# headstage.net
KiCad netlist of a schematic drawn in EAGLE
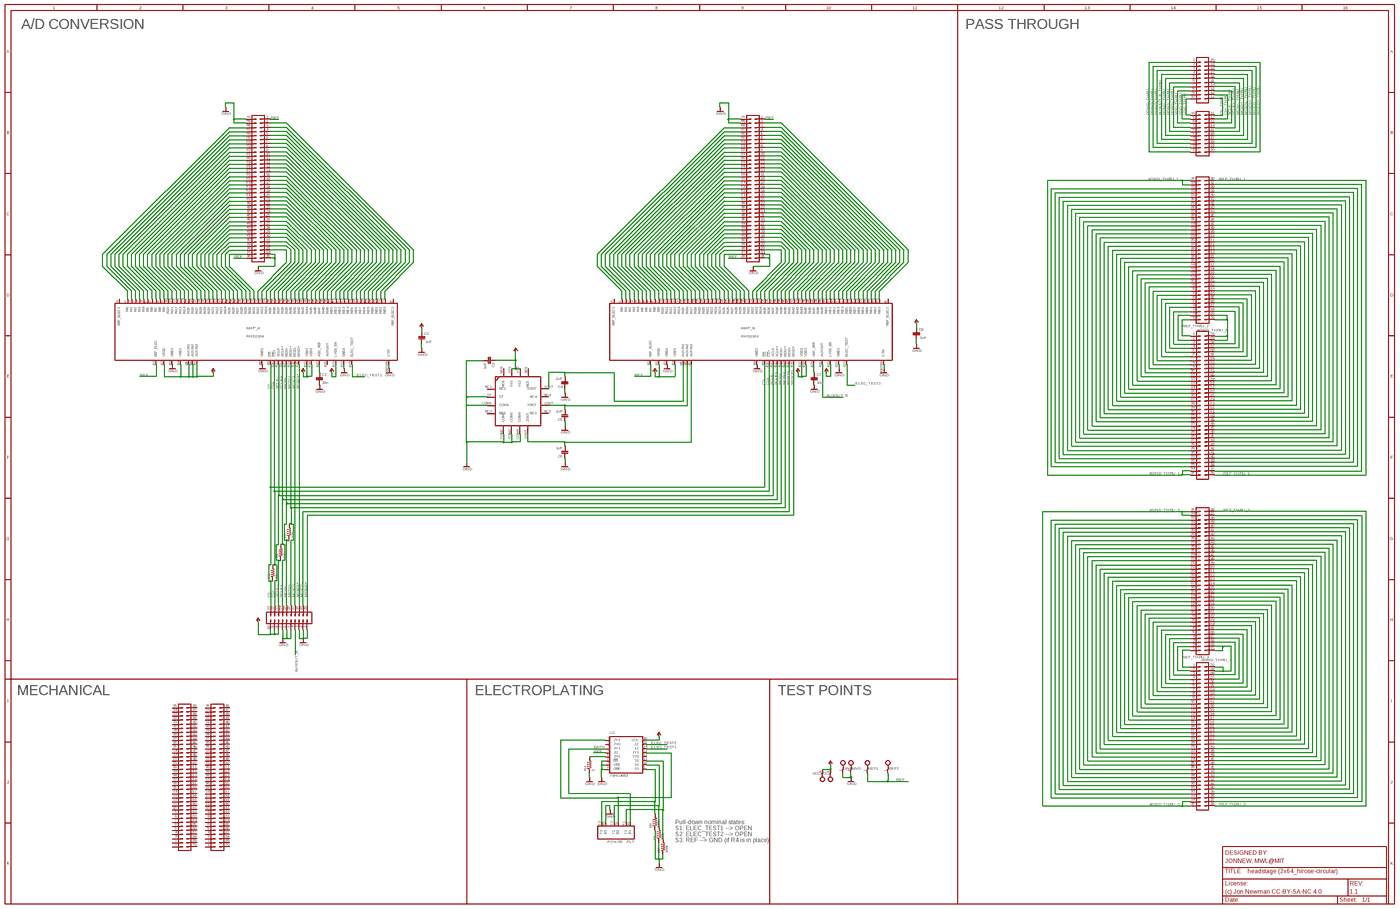
[diagram p0: schematic, sheet 1, overview]
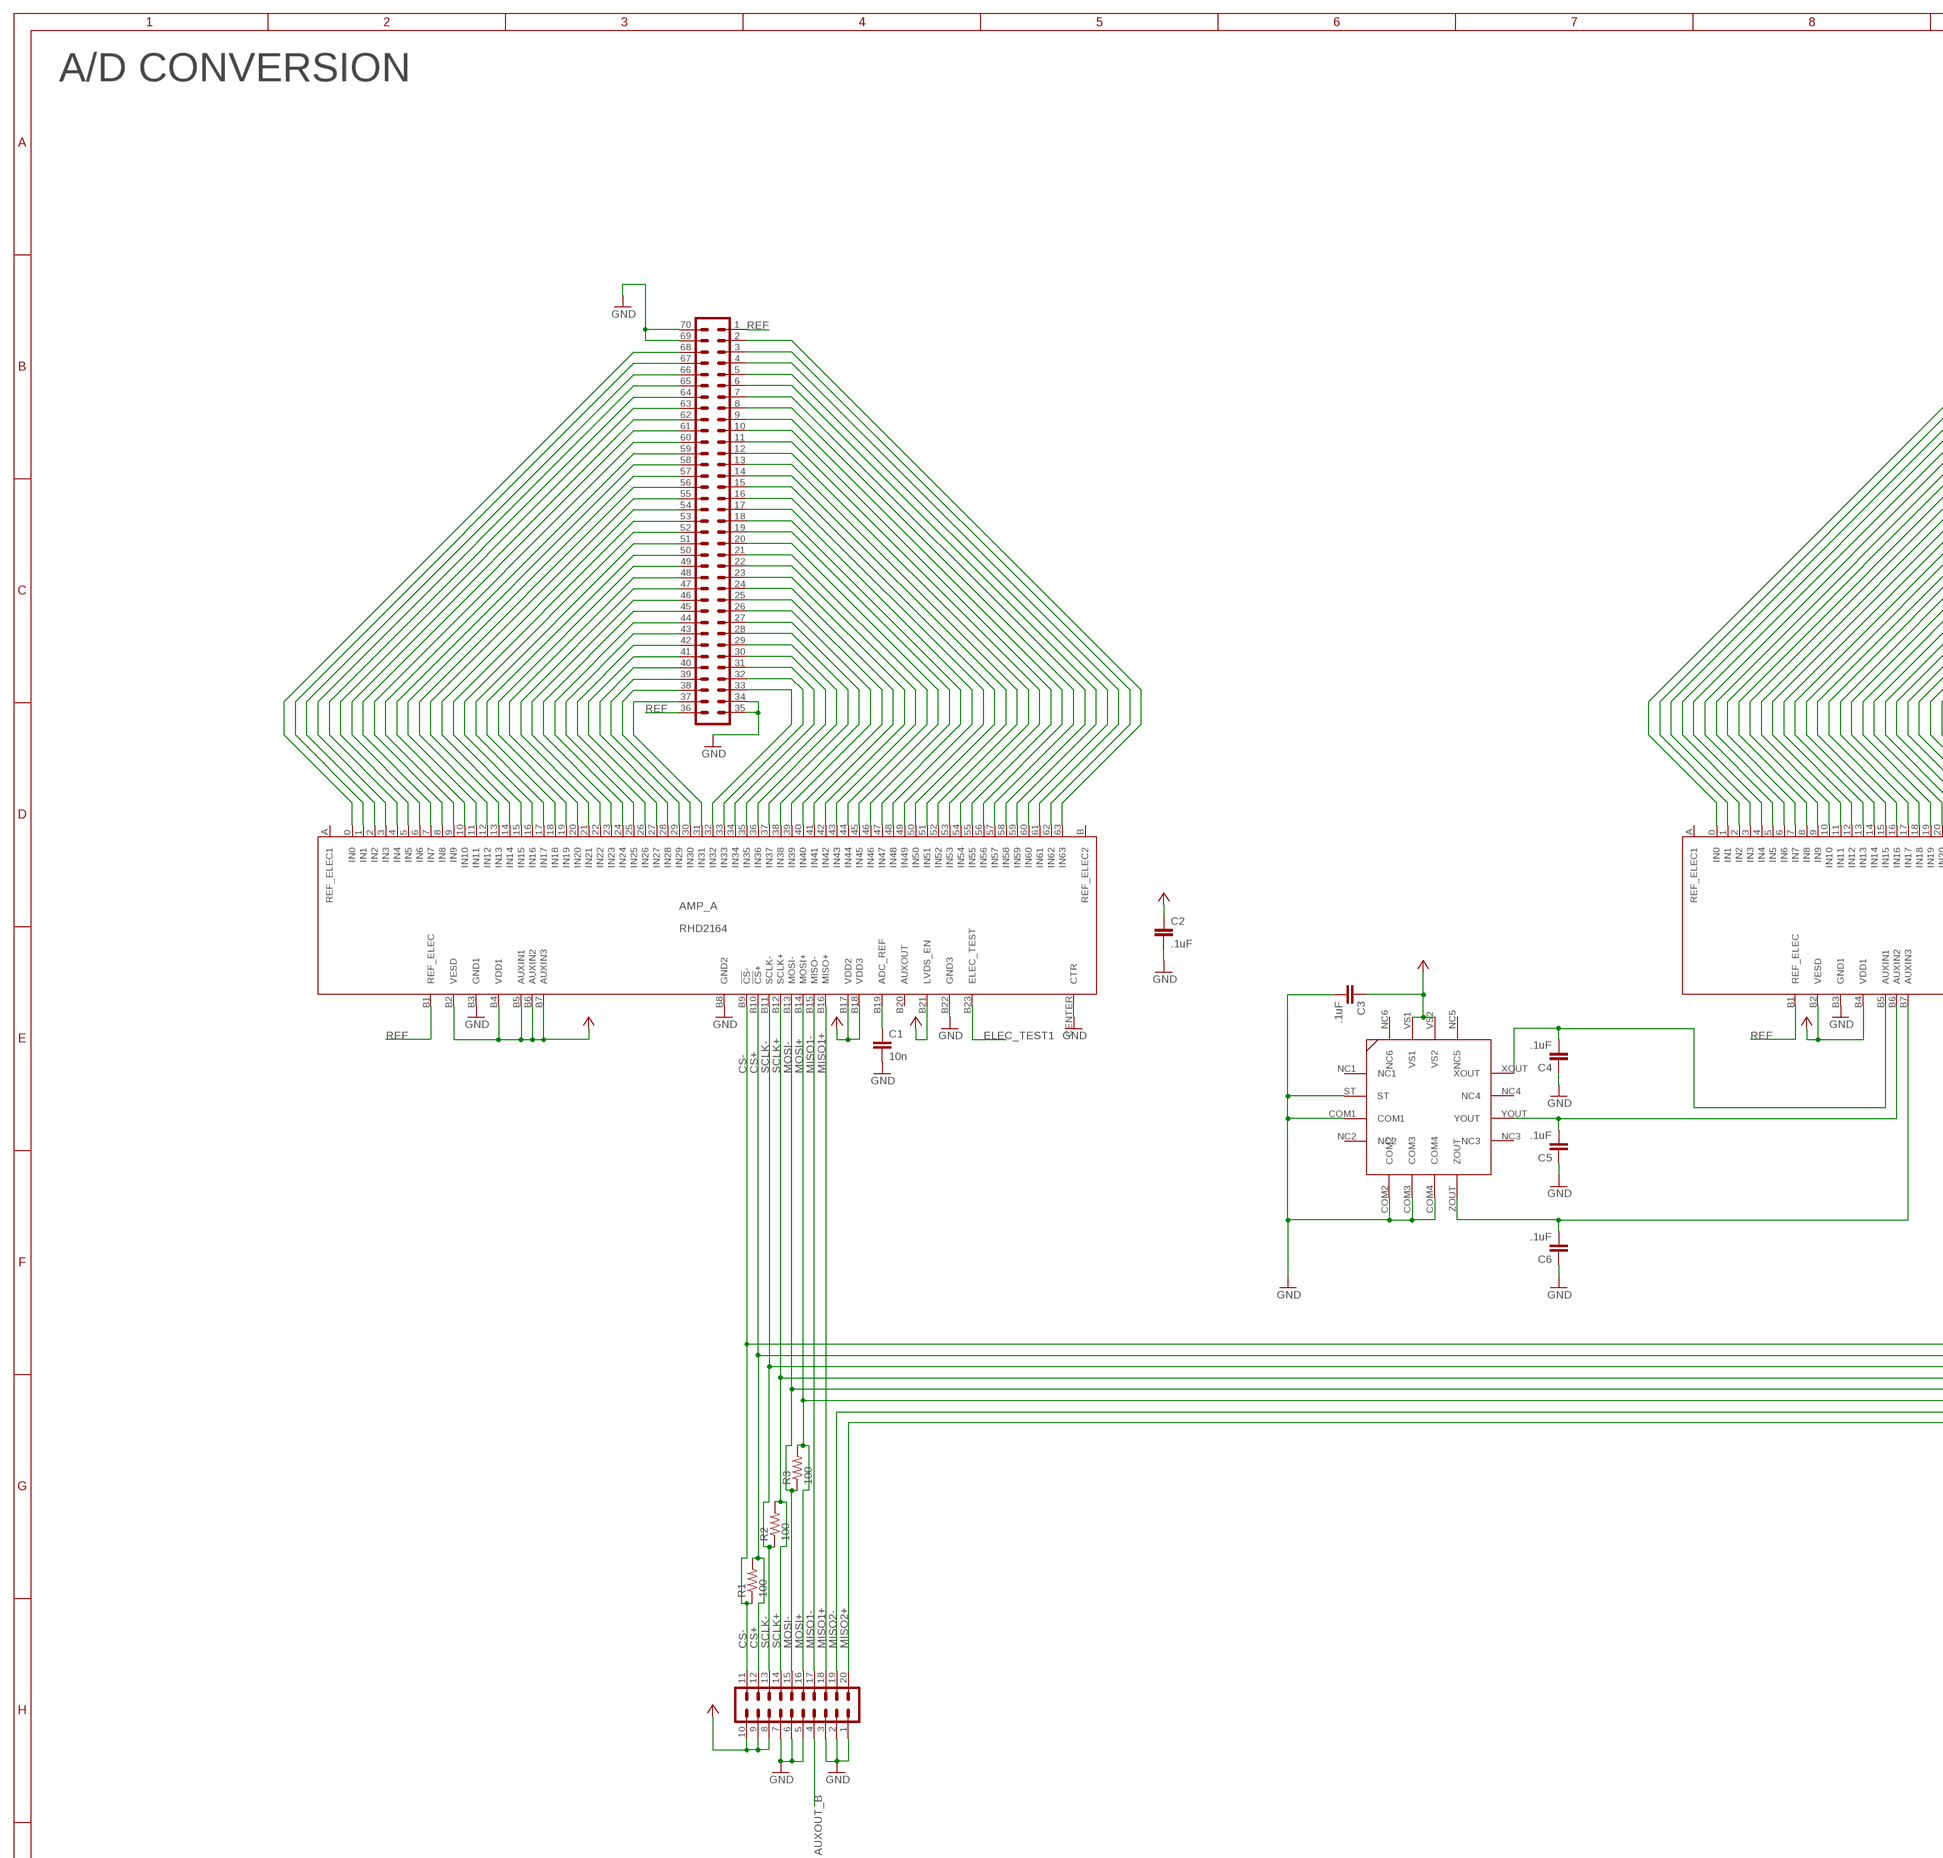
[diagram p1: schematic, sheet 1, part 1 of 4]
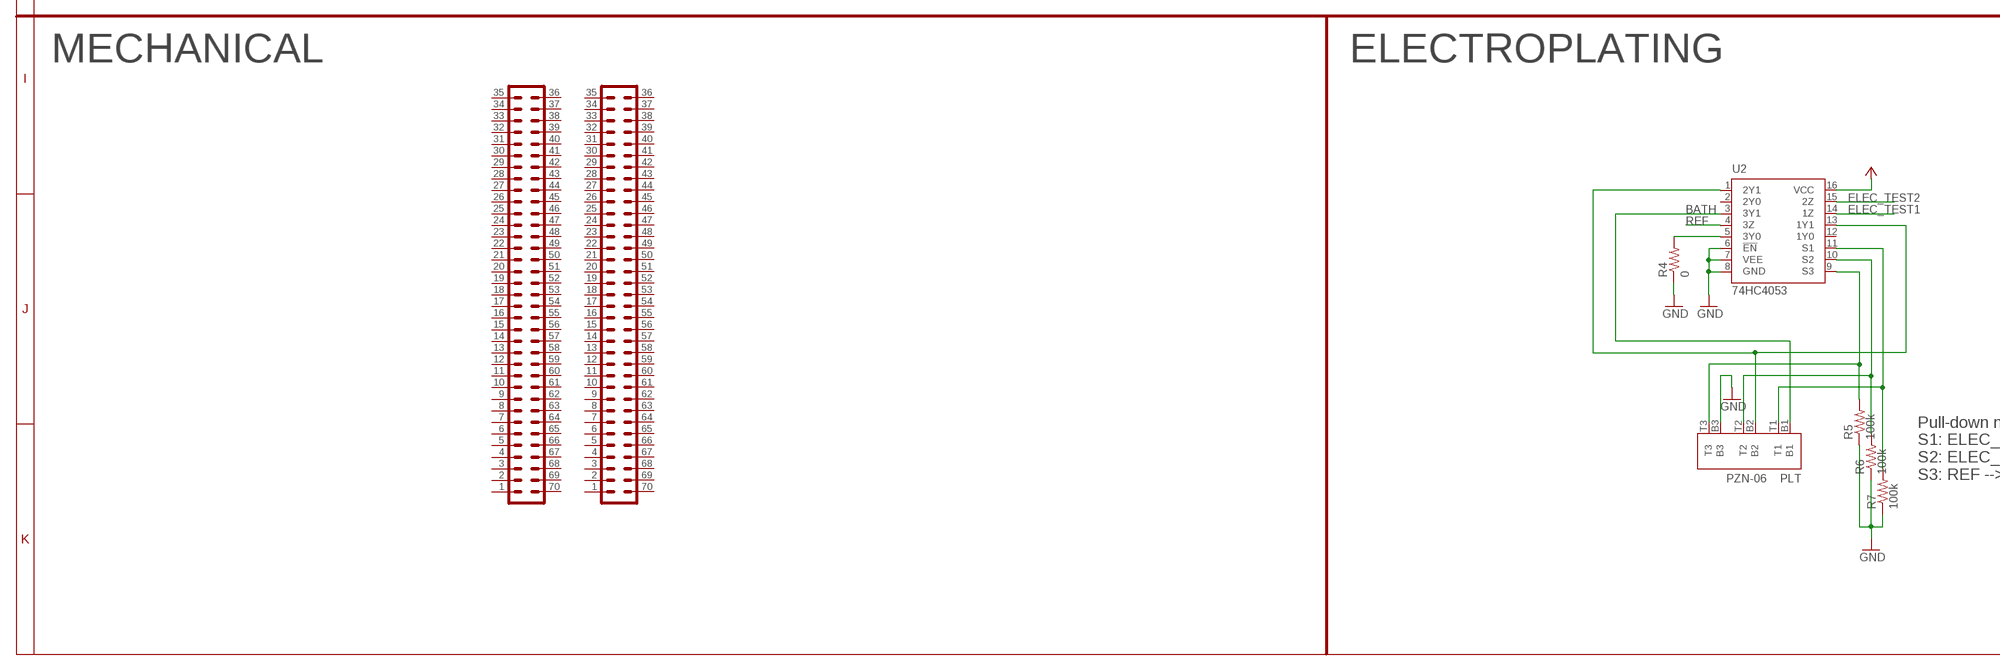
[diagram p2: schematic, sheet 1, part 2 of 4]
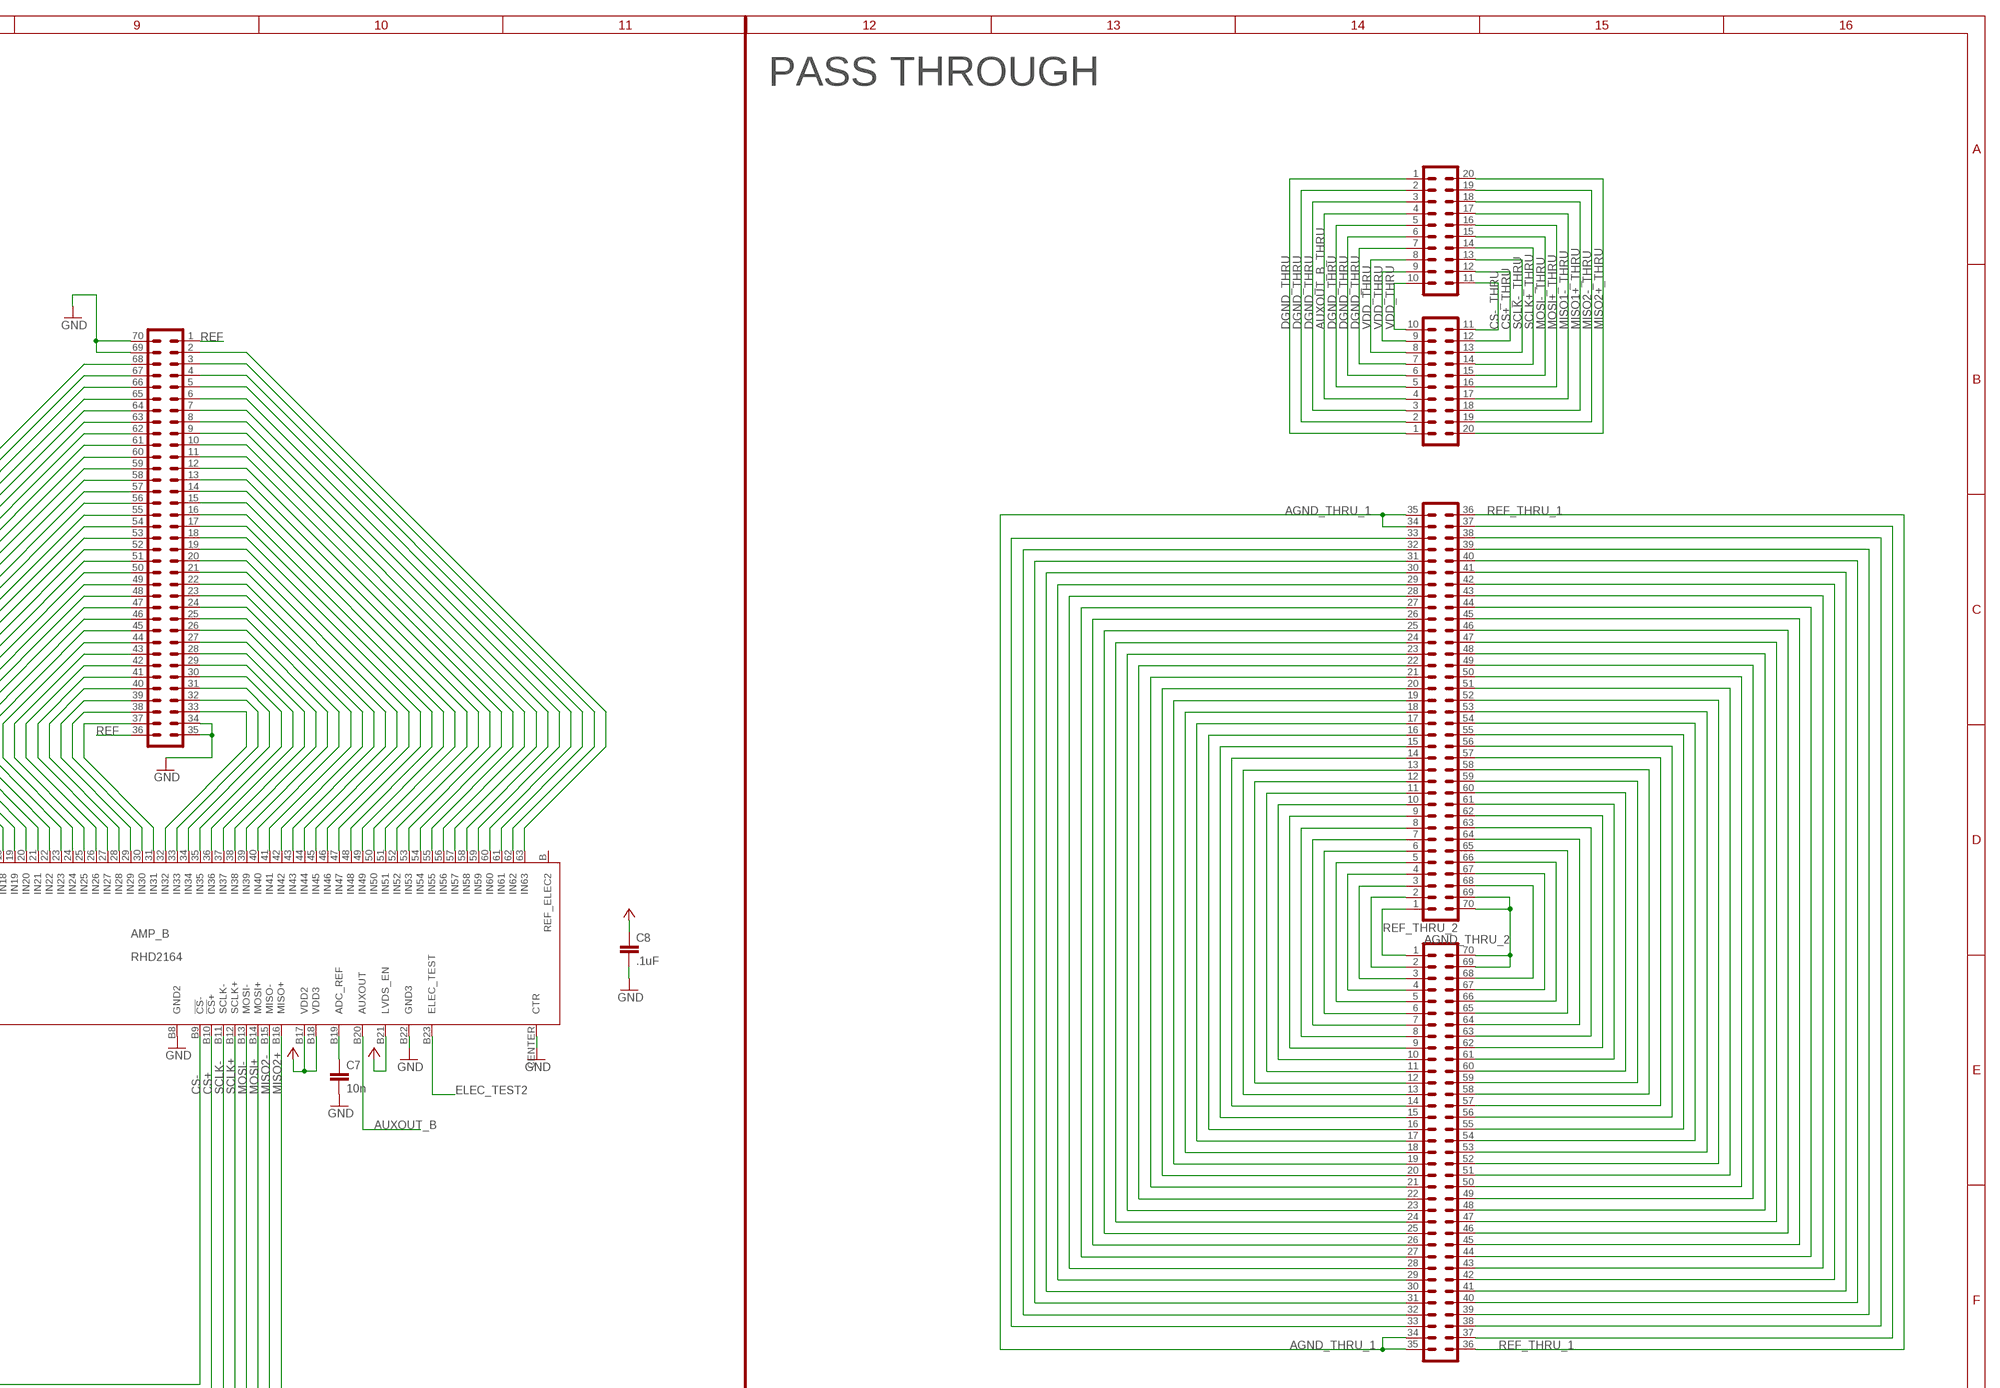
[diagram p3: schematic, sheet 1, part 3 of 4]
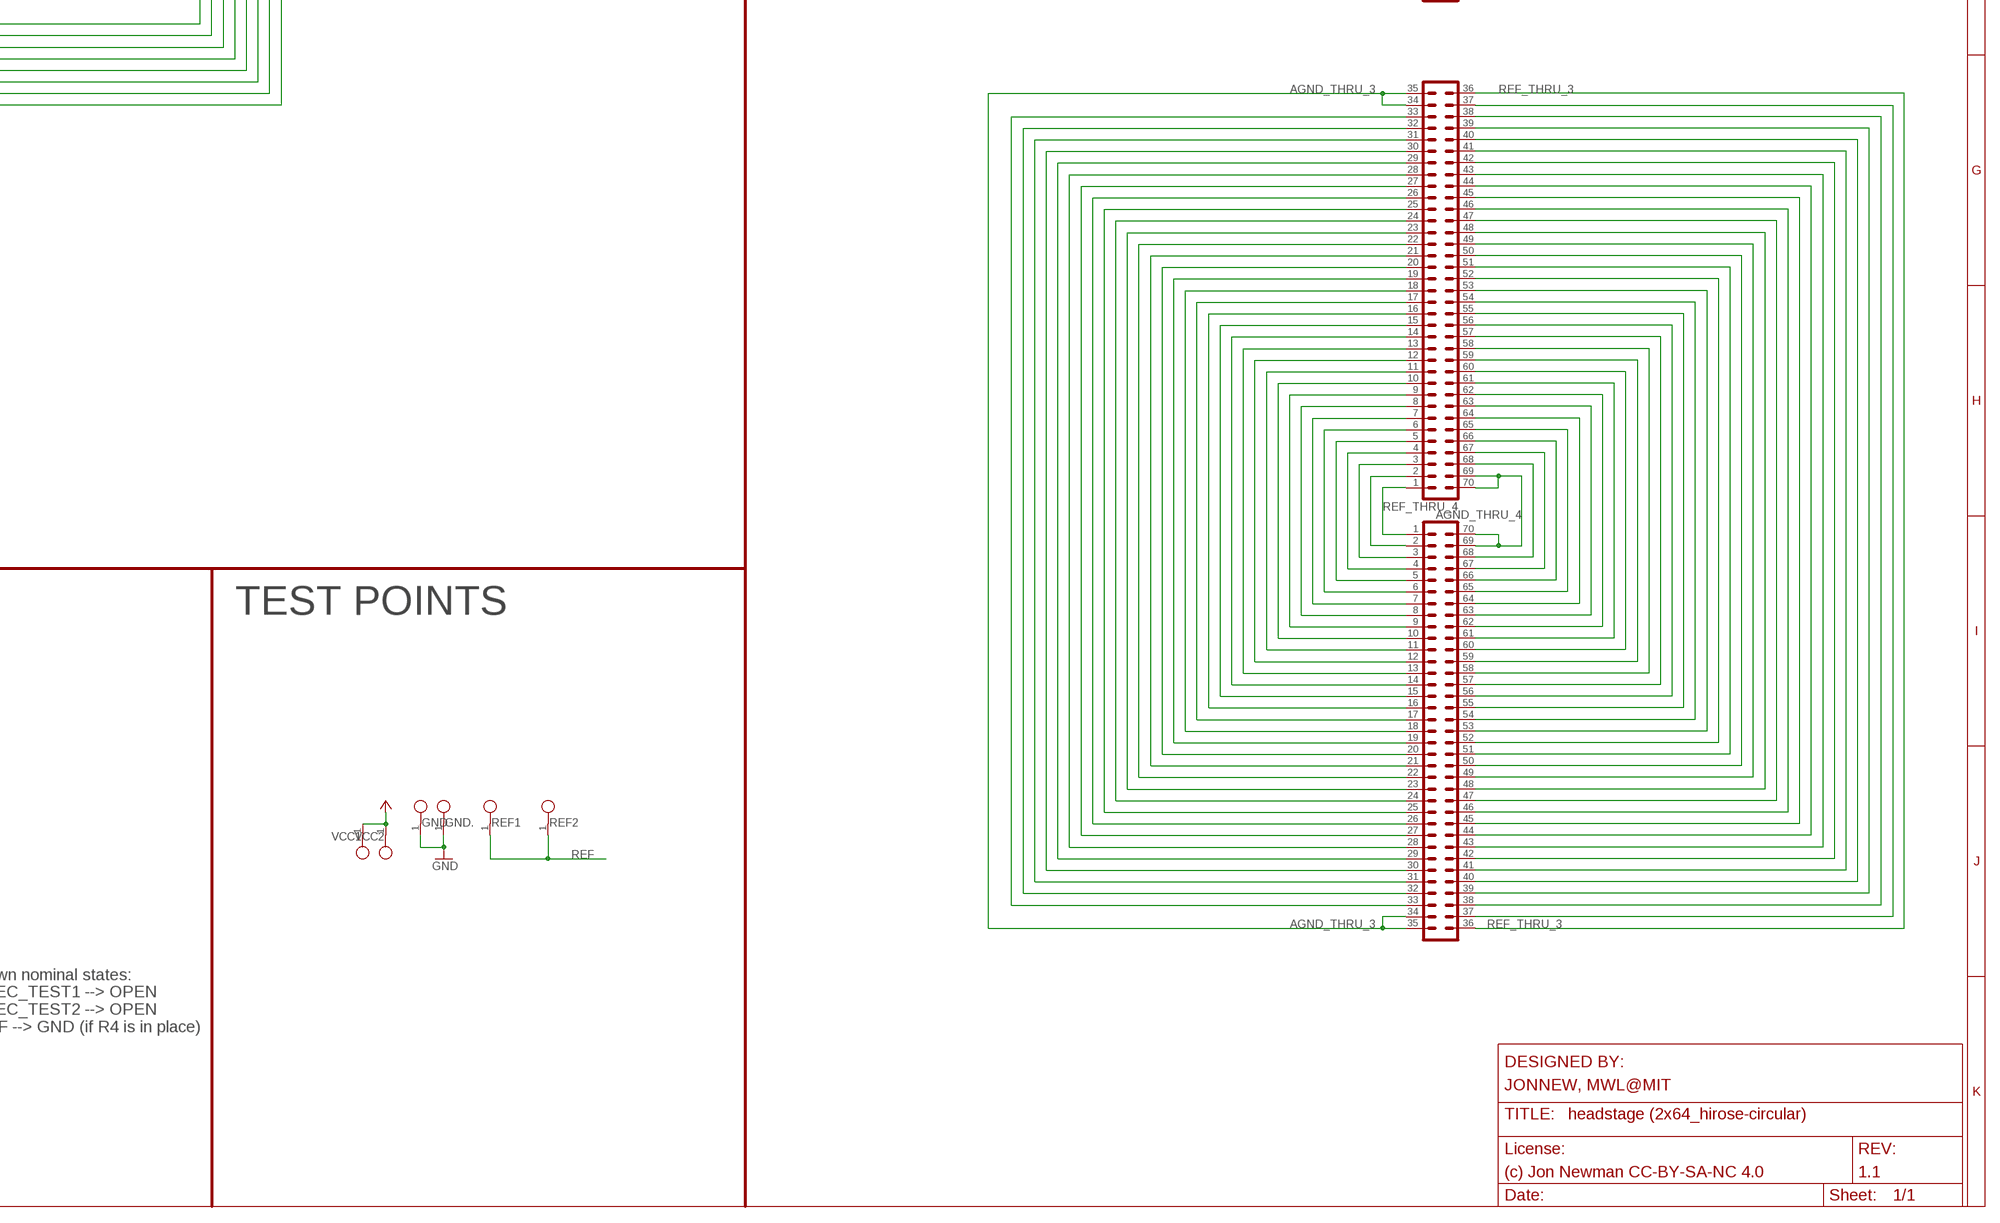
[diagram p4: schematic, sheet 1, part 4 of 4]

(export (version "E")
  (design (tool "Eeschema 10.0.6"))
  (components
    (comp (ref "AIN_BNB")
      (value "DF40REC")
      (footprint "eagle-import:DF40-70REC")
      (libsource (lib "eagle-import") (part "PINHD-2X35_DF40REC"))
    )
    (comp (ref "AIN_BSB")
      (value "DF40REC")
      (footprint "eagle-import:DF40-70REC")
      (libsource (lib "eagle-import") (part "PINHD-2X35_DF40REC"))
    )
    (comp (ref "AMP_A")
      (value "RHD2164")
      (footprint "eagle-import:RHD2164_COB")
      (libsource (lib "eagle-import") (part "RHD2164_COB"))
    )
    (comp (ref "AMP_B")
      (value "RHD2164")
      (footprint "eagle-import:RHD2164_COB")
      (libsource (lib "eagle-import") (part "RHD2164_COB"))
    )
    (comp (ref "ATHRU_BEB")
      (value "DF40REC")
      (footprint "eagle-import:DF40-70REC")
      (libsource (lib "eagle-import") (part "PINHD-2X35_DF40REC"))
    )
    (comp (ref "ATHRU_BWB")
      (value "DF40REC")
      (footprint "eagle-import:DF40-70REC")
      (libsource (lib "eagle-import") (part "PINHD-2X35_DF40REC"))
    )
    (comp (ref "ATHRU_TEB")
      (value "DF40HEAD")
      (footprint "eagle-import:DF40-70HEAD")
      (libsource (lib "eagle-import") (part "PINHD-2X35_DF40HEAD"))
    )
    (comp (ref "ATHRU_TWB")
      (value "DF40HEAD")
      (footprint "eagle-import:DF40-70HEAD")
      (libsource (lib "eagle-import") (part "PINHD-2X35_DF40HEAD"))
    )
    (comp (ref "C1")
      (value "10n")
      (footprint "eagle-import:0201")
      (libsource (lib "eagle-import") (part "C_0201"))
    )
    (comp (ref "C2")
      (value ".1uF")
      (footprint "eagle-import:0402")
      (libsource (lib "eagle-import") (part "C_0402"))
    )
    (comp (ref "C3")
      (value ".1uF")
      (footprint "eagle-import:0402")
      (libsource (lib "eagle-import") (part "headstage_C_0402"))
    )
    (comp (ref "C4")
      (value ".1uF")
      (footprint "eagle-import:0402")
      (libsource (lib "eagle-import") (part "jonnew_C_0402"))
    )
    (comp (ref "C5")
      (value ".1uF")
      (footprint "eagle-import:0402")
      (libsource (lib "eagle-import") (part "jonnew_C_0402"))
    )
    (comp (ref "C6")
      (value ".1uF")
      (footprint "eagle-import:0402")
      (libsource (lib "eagle-import") (part "jonnew_C_0402"))
    )
    (comp (ref "C7")
      (value "10n")
      (footprint "eagle-import:0201")
      (libsource (lib "eagle-import") (part "C_0201"))
    )
    (comp (ref "C8")
      (value ".1uF")
      (footprint "eagle-import:0402")
      (libsource (lib "eagle-import") (part "C_0402"))
    )
    (comp (ref "DIO_TEA")
      (value "DF40HEAD")
      (footprint "eagle-import:DF40-20HEAD")
      (libsource (lib "eagle-import") (part "PINHD-2X10_DF40-20HEAD"))
    )
    (comp (ref "DTHRU_BNA")
      (value "DF40REC")
      (footprint "eagle-import:DF40-20REC")
      (libsource (lib "eagle-import") (part "PINHD-2X10_DF40-20REC"))
    )
    (comp (ref "DTHRU_TNA")
      (value "DF40HEAD")
      (footprint "eagle-import:DF40-20HEAD")
      (libsource (lib "eagle-import") (part "PINHD-2X10_DF40-20HEAD"))
    )
    (comp (ref "GND")
      (value "GND")
      (footprint "eagle-import:TESTPOINT_SMALL")
      (libsource (lib "eagle-import") (part "TESTPOINT_SMALL"))
    )
    (comp (ref "GND.")
      (value "GND")
      (footprint "eagle-import:TESTPOINT_SMALL")
      (libsource (lib "eagle-import") (part "TESTPOINT_SMALL"))
    )
    (comp (ref "MECH_TNB")
      (value "DF40HEAD")
      (footprint "eagle-import:DF40-70HEAD")
      (libsource (lib "eagle-import") (part "PINHD-2X35_DF40HEAD"))
    )
    (comp (ref "MECH_TSB")
      (value "DF40HEAD")
      (footprint "eagle-import:DF40-70HEAD")
      (libsource (lib "eagle-import") (part "PINHD-2X35_DF40HEAD"))
    )
    (comp (ref "PLT")
      (value "PZN-06")
      (footprint "eagle-import:OMNETICS_PZN-06-AA")
      (libsource (lib "eagle-import") (part "OMNETICS_PZN-06_SMD"))
    )
    (comp (ref "R1")
      (value "100")
      (footprint "eagle-import:0201")
      (libsource (lib "eagle-import") (part "jonnew_R_0201"))
    )
    (comp (ref "R2")
      (value "100")
      (footprint "eagle-import:0201")
      (libsource (lib "eagle-import") (part "jonnew_R_0201"))
    )
    (comp (ref "R3")
      (value "100")
      (footprint "eagle-import:0201")
      (libsource (lib "eagle-import") (part "jonnew_R_0201"))
    )
    (comp (ref "R4")
      (value "0")
      (footprint "eagle-import:0402")
      (libsource (lib "eagle-import") (part "R_0402"))
    )
    (comp (ref "R5")
      (value "100k")
      (footprint "eagle-import:0201")
      (libsource (lib "eagle-import") (part "R_0201"))
    )
    (comp (ref "R6")
      (value "100k")
      (footprint "eagle-import:0201")
      (libsource (lib "eagle-import") (part "R_0201"))
    )
    (comp (ref "R7")
      (value "100k")
      (footprint "eagle-import:0201")
      (libsource (lib "eagle-import") (part "R_0201"))
    )
    (comp (ref "REF1")
      (value "REF")
      (footprint "eagle-import:TESTPOINT_SMALL")
      (libsource (lib "eagle-import") (part "TESTPOINT_SMALL"))
    )
    (comp (ref "REF2")
      (value "REF")
      (footprint "eagle-import:TESTPOINT_SMALL")
      (libsource (lib "eagle-import") (part "TESTPOINT_SMALL"))
    )
    (comp (ref "U1")
      (value "ADXL335")
      (footprint "eagle-import:ADXL335")
      (libsource (lib "eagle-import") (part "ADXL335"))
    )
    (comp (ref "U2")
      (value "74HC4053")
      (footprint "eagle-import:TSSOP-16")
      (libsource (lib "eagle-import") (part "74HC4053_TSSOP-16"))
    )
    (comp (ref "VCC1")
      (value "VCC")
      (footprint "eagle-import:TESTPOINT_SMALL")
      (libsource (lib "eagle-import") (part "TESTPOINT_SMALL"))
    )
    (comp (ref "VCC2")
      (value "VCC")
      (footprint "eagle-import:TESTPOINT_SMALL")
      (libsource (lib "eagle-import") (part "TESTPOINT_SMALL"))
    )
  )
  (nets
    (net (code "1") (name "/AGND_THRU_1") (class "Default")
      (node (ref "ATHRU_BWB") (pin "34") (pinfunction "34_34") (pintype "bidirectional"))
      (node (ref "ATHRU_BWB") (pin "35") (pinfunction "35_35") (pintype "bidirectional"))
      (node (ref "ATHRU_TWB") (pin "34") (pinfunction "34_34") (pintype "bidirectional"))
      (node (ref "ATHRU_TWB") (pin "35") (pinfunction "35_35") (pintype "bidirectional"))
    )
    (net (code "2") (name "/AGND_THRU_2") (class "Default")
      (node (ref "ATHRU_BWB") (pin "69") (pinfunction "69_69") (pintype "bidirectional"))
      (node (ref "ATHRU_BWB") (pin "70") (pinfunction "70_70") (pintype "bidirectional"))
      (node (ref "ATHRU_TWB") (pin "69") (pinfunction "69_69") (pintype "bidirectional"))
      (node (ref "ATHRU_TWB") (pin "70") (pinfunction "70_70") (pintype "bidirectional"))
    )
    (net (code "3") (name "/AGND_THRU_3") (class "Default")
      (node (ref "ATHRU_BEB") (pin "34") (pinfunction "34_34") (pintype "bidirectional"))
      (node (ref "ATHRU_BEB") (pin "35") (pinfunction "35_35") (pintype "bidirectional"))
      (node (ref "ATHRU_TEB") (pin "34") (pinfunction "34_34") (pintype "bidirectional"))
      (node (ref "ATHRU_TEB") (pin "35") (pinfunction "35_35") (pintype "bidirectional"))
    )
    (net (code "4") (name "/AGND_THRU_4") (class "Default")
      (node (ref "ATHRU_BEB") (pin "69") (pinfunction "69_69") (pintype "bidirectional"))
      (node (ref "ATHRU_BEB") (pin "70") (pinfunction "70_70") (pintype "bidirectional"))
      (node (ref "ATHRU_TEB") (pin "69") (pinfunction "69_69") (pintype "bidirectional"))
      (node (ref "ATHRU_TEB") (pin "70") (pinfunction "70_70") (pintype "bidirectional"))
    )
    (net (code "5") (name "/AUXOUT_B") (class "Default")
      (node (ref "AMP_B") (pin "B20") (pinfunction "AUXOUT_B20") (pintype "tri_state"))
      (node (ref "DIO_TEA") (pin "4") (pinfunction "4_4") (pintype "bidirectional"))
    )
    (net (code "6") (name "/AUXOUT_B_THRU") (class "Default")
      (node (ref "DTHRU_BNA") (pin "4") (pinfunction "4_4") (pintype "bidirectional"))
      (node (ref "DTHRU_TNA") (pin "4") (pinfunction "4_4") (pintype "bidirectional"))
    )
    (net (code "7") (name "/BATH") (class "Default")
      (node (ref "PLT") (pin "B1") (pinfunction "B1_B1") (pintype "bidirectional"))
      (node (ref "U2") (pin "3") (pinfunction "3Y1_3") (pintype "bidirectional"))
    )
    (net (code "8") (name "/CS+") (class "Default")
      (node (ref "AMP_A") (pin "B10") (pinfunction "~{CS}+_B10") (pintype "input"))
      (node (ref "AMP_B") (pin "B10") (pinfunction "~{CS}+_B10") (pintype "input"))
      (node (ref "DIO_TEA") (pin "12") (pinfunction "12_12") (pintype "bidirectional"))
      (node (ref "R1") (pin "2") (pinfunction "2_2") (pintype "passive"))
    )
    (net (code "9") (name "/CS+_THRU") (class "Default")
      (node (ref "DTHRU_BNA") (pin "12") (pinfunction "12_12") (pintype "bidirectional"))
      (node (ref "DTHRU_TNA") (pin "12") (pinfunction "12_12") (pintype "bidirectional"))
    )
    (net (code "10") (name "/CS-") (class "Default")
      (node (ref "AMP_A") (pin "B9") (pinfunction "~{CS}-_B9") (pintype "input"))
      (node (ref "AMP_B") (pin "B9") (pinfunction "~{CS}-_B9") (pintype "input"))
      (node (ref "DIO_TEA") (pin "11") (pinfunction "11_11") (pintype "bidirectional"))
      (node (ref "R1") (pin "1") (pinfunction "1_1") (pintype "passive"))
    )
    (net (code "11") (name "/CS-_THRU") (class "Default")
      (node (ref "DTHRU_BNA") (pin "11") (pinfunction "11_11") (pintype "bidirectional"))
      (node (ref "DTHRU_TNA") (pin "11") (pinfunction "11_11") (pintype "bidirectional"))
    )
    (net (code "12") (name "/DGND_THRU") (class "Default")
      (node (ref "DTHRU_BNA") (pin "1") (pinfunction "1_1") (pintype "bidirectional"))
      (node (ref "DTHRU_BNA") (pin "2") (pinfunction "2_2") (pintype "bidirectional"))
      (node (ref "DTHRU_BNA") (pin "3") (pinfunction "3_3") (pintype "bidirectional"))
      (node (ref "DTHRU_BNA") (pin "5") (pinfunction "5_5") (pintype "bidirectional"))
      (node (ref "DTHRU_BNA") (pin "6") (pinfunction "6_6") (pintype "bidirectional"))
      (node (ref "DTHRU_BNA") (pin "7") (pinfunction "7_7") (pintype "bidirectional"))
      (node (ref "DTHRU_TNA") (pin "1") (pinfunction "1_1") (pintype "bidirectional"))
      (node (ref "DTHRU_TNA") (pin "2") (pinfunction "2_2") (pintype "bidirectional"))
      (node (ref "DTHRU_TNA") (pin "3") (pinfunction "3_3") (pintype "bidirectional"))
      (node (ref "DTHRU_TNA") (pin "5") (pinfunction "5_5") (pintype "bidirectional"))
      (node (ref "DTHRU_TNA") (pin "6") (pinfunction "6_6") (pintype "bidirectional"))
      (node (ref "DTHRU_TNA") (pin "7") (pinfunction "7_7") (pintype "bidirectional"))
    )
    (net (code "13") (name "/ELEC_TEST1") (class "Default")
      (node (ref "AMP_A") (pin "B23") (pinfunction "ELEC_TEST_B23") (pintype "input"))
      (node (ref "U2") (pin "14") (pinfunction "1Z_14") (pintype "bidirectional"))
    )
    (net (code "14") (name "/ELEC_TEST2") (class "Default")
      (node (ref "AMP_B") (pin "B23") (pinfunction "ELEC_TEST_B23") (pintype "input"))
      (node (ref "U2") (pin "15") (pinfunction "2Z_15") (pintype "bidirectional"))
    )
    (net (code "15") (name "/MISO1+") (class "Default")
      (node (ref "AMP_A") (pin "B16") (pinfunction "MISO+_B16") (pintype "output"))
      (node (ref "DIO_TEA") (pin "18") (pinfunction "18_18") (pintype "bidirectional"))
    )
    (net (code "16") (name "/MISO1+_THRU") (class "Default")
      (node (ref "DTHRU_BNA") (pin "18") (pinfunction "18_18") (pintype "bidirectional"))
      (node (ref "DTHRU_TNA") (pin "18") (pinfunction "18_18") (pintype "bidirectional"))
    )
    (net (code "17") (name "/MISO1-") (class "Default")
      (node (ref "AMP_A") (pin "B15") (pinfunction "MISO-_B15") (pintype "output"))
      (node (ref "DIO_TEA") (pin "17") (pinfunction "17_17") (pintype "bidirectional"))
    )
    (net (code "18") (name "/MISO1-_THRU") (class "Default")
      (node (ref "DTHRU_BNA") (pin "17") (pinfunction "17_17") (pintype "bidirectional"))
      (node (ref "DTHRU_TNA") (pin "17") (pinfunction "17_17") (pintype "bidirectional"))
    )
    (net (code "19") (name "/MISO2+") (class "Default")
      (node (ref "AMP_B") (pin "B16") (pinfunction "MISO+_B16") (pintype "output"))
      (node (ref "DIO_TEA") (pin "20") (pinfunction "20_20") (pintype "bidirectional"))
    )
    (net (code "20") (name "/MISO2+_THRU") (class "Default")
      (node (ref "DTHRU_BNA") (pin "20") (pinfunction "20_20") (pintype "bidirectional"))
      (node (ref "DTHRU_TNA") (pin "20") (pinfunction "20_20") (pintype "bidirectional"))
    )
    (net (code "21") (name "/MISO2-") (class "Default")
      (node (ref "AMP_B") (pin "B15") (pinfunction "MISO-_B15") (pintype "output"))
      (node (ref "DIO_TEA") (pin "19") (pinfunction "19_19") (pintype "bidirectional"))
    )
    (net (code "22") (name "/MISO2-_THRU") (class "Default")
      (node (ref "DTHRU_BNA") (pin "19") (pinfunction "19_19") (pintype "bidirectional"))
      (node (ref "DTHRU_TNA") (pin "19") (pinfunction "19_19") (pintype "bidirectional"))
    )
    (net (code "23") (name "/MOSI+") (class "Default")
      (node (ref "AMP_A") (pin "B14") (pinfunction "MOSI+_B14") (pintype "input"))
      (node (ref "AMP_B") (pin "B14") (pinfunction "MOSI+_B14") (pintype "input"))
      (node (ref "DIO_TEA") (pin "16") (pinfunction "16_16") (pintype "bidirectional"))
      (node (ref "R3") (pin "2") (pinfunction "2_2") (pintype "passive"))
    )
    (net (code "24") (name "/MOSI+_THRU") (class "Default")
      (node (ref "DTHRU_BNA") (pin "16") (pinfunction "16_16") (pintype "bidirectional"))
      (node (ref "DTHRU_TNA") (pin "16") (pinfunction "16_16") (pintype "bidirectional"))
    )
    (net (code "25") (name "/MOSI-") (class "Default")
      (node (ref "AMP_A") (pin "B13") (pinfunction "MOSI-_B13") (pintype "input"))
      (node (ref "AMP_B") (pin "B13") (pinfunction "MOSI-_B13") (pintype "input"))
      (node (ref "DIO_TEA") (pin "15") (pinfunction "15_15") (pintype "bidirectional"))
      (node (ref "R3") (pin "1") (pinfunction "1_1") (pintype "passive"))
    )
    (net (code "26") (name "/MOSI-_THRU") (class "Default")
      (node (ref "DTHRU_BNA") (pin "15") (pinfunction "15_15") (pintype "bidirectional"))
      (node (ref "DTHRU_TNA") (pin "15") (pinfunction "15_15") (pintype "bidirectional"))
    )
    (net (code "27") (name "/REF") (class "Default")
      (node (ref "AIN_BNB") (pin "1") (pinfunction "1_1") (pintype "bidirectional"))
      (node (ref "AIN_BNB") (pin "36") (pinfunction "36_36") (pintype "bidirectional"))
      (node (ref "AIN_BSB") (pin "1") (pinfunction "1_1") (pintype "bidirectional"))
      (node (ref "AIN_BSB") (pin "36") (pinfunction "36_36") (pintype "bidirectional"))
      (node (ref "AMP_A") (pin "B1") (pinfunction "REF_ELEC_B1") (pintype "input"))
      (node (ref "AMP_B") (pin "B1") (pinfunction "REF_ELEC_B1") (pintype "input"))
      (node (ref "REF1") (pin "1") (pinfunction "1_1") (pintype "passive"))
      (node (ref "REF2") (pin "1") (pinfunction "1_1") (pintype "passive"))
      (node (ref "U2") (pin "4") (pinfunction "3Z_4") (pintype "bidirectional"))
    )
    (net (code "28") (name "/REF_THRU_1") (class "Default")
      (node (ref "ATHRU_BWB") (pin "36") (pinfunction "36_36") (pintype "bidirectional"))
      (node (ref "ATHRU_TWB") (pin "36") (pinfunction "36_36") (pintype "bidirectional"))
    )
    (net (code "29") (name "/REF_THRU_2") (class "Default")
      (node (ref "ATHRU_BWB") (pin "1") (pinfunction "1_1") (pintype "bidirectional"))
      (node (ref "ATHRU_TWB") (pin "1") (pinfunction "1_1") (pintype "bidirectional"))
    )
    (net (code "30") (name "/REF_THRU_3") (class "Default")
      (node (ref "ATHRU_BEB") (pin "36") (pinfunction "36_36") (pintype "bidirectional"))
      (node (ref "ATHRU_TEB") (pin "36") (pinfunction "36_36") (pintype "bidirectional"))
    )
    (net (code "31") (name "/REF_THRU_4") (class "Default")
      (node (ref "ATHRU_BEB") (pin "1") (pinfunction "1_1") (pintype "bidirectional"))
      (node (ref "ATHRU_TEB") (pin "1") (pinfunction "1_1") (pintype "bidirectional"))
    )
    (net (code "32") (name "/SCLK+") (class "Default")
      (node (ref "AMP_A") (pin "B12") (pinfunction "SCLK+_B12") (pintype "input"))
      (node (ref "AMP_B") (pin "B12") (pinfunction "SCLK+_B12") (pintype "input"))
      (node (ref "DIO_TEA") (pin "14") (pinfunction "14_14") (pintype "bidirectional"))
      (node (ref "R2") (pin "2") (pinfunction "2_2") (pintype "passive"))
    )
    (net (code "33") (name "/SCLK+_THRU") (class "Default")
      (node (ref "DTHRU_BNA") (pin "14") (pinfunction "14_14") (pintype "bidirectional"))
      (node (ref "DTHRU_TNA") (pin "14") (pinfunction "14_14") (pintype "bidirectional"))
    )
    (net (code "34") (name "/SCLK-") (class "Default")
      (node (ref "AMP_A") (pin "B11") (pinfunction "SCLK-_B11") (pintype "input"))
      (node (ref "AMP_B") (pin "B11") (pinfunction "SCLK-_B11") (pintype "input"))
      (node (ref "DIO_TEA") (pin "13") (pinfunction "13_13") (pintype "bidirectional"))
      (node (ref "R2") (pin "1") (pinfunction "1_1") (pintype "passive"))
    )
    (net (code "35") (name "/SCLK-_THRU") (class "Default")
      (node (ref "DTHRU_BNA") (pin "13") (pinfunction "13_13") (pintype "bidirectional"))
      (node (ref "DTHRU_TNA") (pin "13") (pinfunction "13_13") (pintype "bidirectional"))
    )
    (net (code "36") (name "/VDD_THRU") (class "Default")
      (node (ref "DTHRU_BNA") (pin "10") (pinfunction "10_10") (pintype "bidirectional"))
      (node (ref "DTHRU_BNA") (pin "8") (pinfunction "8_8") (pintype "bidirectional"))
      (node (ref "DTHRU_BNA") (pin "9") (pinfunction "9_9") (pintype "bidirectional"))
      (node (ref "DTHRU_TNA") (pin "10") (pinfunction "10_10") (pintype "bidirectional"))
      (node (ref "DTHRU_TNA") (pin "8") (pinfunction "8_8") (pintype "bidirectional"))
      (node (ref "DTHRU_TNA") (pin "9") (pinfunction "9_9") (pintype "bidirectional"))
    )
    (net (code "37") (name "GND") (class "Default")
      (node (ref "AIN_BNB") (pin "34") (pinfunction "34_34") (pintype "bidirectional"))
      (node (ref "AIN_BNB") (pin "35") (pinfunction "35_35") (pintype "bidirectional"))
      (node (ref "AIN_BNB") (pin "69") (pinfunction "69_69") (pintype "bidirectional"))
      (node (ref "AIN_BNB") (pin "70") (pinfunction "70_70") (pintype "bidirectional"))
      (node (ref "AIN_BSB") (pin "34") (pinfunction "34_34") (pintype "bidirectional"))
      (node (ref "AIN_BSB") (pin "35") (pinfunction "35_35") (pintype "bidirectional"))
      (node (ref "AIN_BSB") (pin "69") (pinfunction "69_69") (pintype "bidirectional"))
      (node (ref "AIN_BSB") (pin "70") (pinfunction "70_70") (pintype "bidirectional"))
      (node (ref "AMP_A") (pin "B22") (pinfunction "GND3_B22") (pintype "power_in"))
      (node (ref "AMP_A") (pin "B3") (pinfunction "GND1_B3") (pintype "power_in"))
      (node (ref "AMP_A") (pin "B8") (pinfunction "GND2_B8") (pintype "power_in"))
      (node (ref "AMP_A") (pin "CENTER") (pinfunction "CTR_CENTER") (pintype "power_in"))
      (node (ref "AMP_B") (pin "B22") (pinfunction "GND3_B22") (pintype "power_in"))
      (node (ref "AMP_B") (pin "B3") (pinfunction "GND1_B3") (pintype "power_in"))
      (node (ref "AMP_B") (pin "B8") (pinfunction "GND2_B8") (pintype "power_in"))
      (node (ref "AMP_B") (pin "CENTER") (pinfunction "CTR_CENTER") (pintype "power_in"))
      (node (ref "C1") (pin "2") (pinfunction "2_2") (pintype "passive"))
      (node (ref "C2") (pin "2") (pinfunction "2_2") (pintype "passive"))
      (node (ref "C3") (pin "2") (pinfunction "2_2") (pintype "passive"))
      (node (ref "C4") (pin "1") (pinfunction "1_1") (pintype "passive"))
      (node (ref "C5") (pin "1") (pinfunction "1_1") (pintype "passive"))
      (node (ref "C6") (pin "1") (pinfunction "1_1") (pintype "passive"))
      (node (ref "C7") (pin "2") (pinfunction "2_2") (pintype "passive"))
      (node (ref "C8") (pin "2") (pinfunction "2_2") (pintype "passive"))
      (node (ref "DIO_TEA") (pin "1") (pinfunction "1_1") (pintype "bidirectional"))
      (node (ref "DIO_TEA") (pin "2") (pinfunction "2_2") (pintype "bidirectional"))
      (node (ref "DIO_TEA") (pin "3") (pinfunction "3_3") (pintype "bidirectional"))
      (node (ref "DIO_TEA") (pin "5") (pinfunction "5_5") (pintype "bidirectional"))
      (node (ref "DIO_TEA") (pin "6") (pinfunction "6_6") (pintype "bidirectional"))
      (node (ref "DIO_TEA") (pin "7") (pinfunction "7_7") (pintype "bidirectional"))
      (node (ref "GND") (pin "1") (pinfunction "1_1") (pintype "passive"))
      (node (ref "GND.") (pin "1") (pinfunction "1_1") (pintype "passive"))
      (node (ref "PLT") (pin "B3") (pinfunction "B3_B3") (pintype "bidirectional"))
      (node (ref "R4") (pin "1") (pinfunction "1_1") (pintype "passive"))
      (node (ref "R5") (pin "1") (pinfunction "1_1") (pintype "passive"))
      (node (ref "R6") (pin "1") (pinfunction "1_1") (pintype "passive"))
      (node (ref "R7") (pin "1") (pinfunction "1_1") (pintype "passive"))
      (node (ref "U1") (pin "COM1") (pinfunction "COM1_COM1") (pintype "bidirectional"))
      (node (ref "U1") (pin "COM2") (pinfunction "COM2_COM2") (pintype "bidirectional"))
      (node (ref "U1") (pin "COM3") (pinfunction "COM3_COM3") (pintype "bidirectional"))
      (node (ref "U1") (pin "COM4") (pinfunction "COM4_COM4") (pintype "bidirectional"))
      (node (ref "U1") (pin "ST") (pinfunction "ST_ST") (pintype "bidirectional"))
      (node (ref "U2") (pin "6") (pinfunction "~{EN}_6") (pintype "input"))
      (node (ref "U2") (pin "7") (pinfunction "VEE_7") (pintype "power_in"))
      (node (ref "U2") (pin "8") (pinfunction "GND_8") (pintype "power_in"))
    )
    (net (code "38") (name "Net-(AMP_A-ADC_REF)") (class "Default")
      (node (ref "AMP_A") (pin "B19") (pinfunction "ADC_REF_B19") (pintype "passive"))
      (node (ref "C1") (pin "1") (pinfunction "1_1") (pintype "passive"))
    )
    (net (code "39") (name "Net-(AMP_A-IN0)") (class "Default")
      (node (ref "AIN_BNB") (pin "68") (pinfunction "68_68") (pintype "bidirectional"))
      (node (ref "AMP_A") (pin "0") (pinfunction "IN0_0") (pintype "input"))
    )
    (net (code "40") (name "Net-(AMP_A-IN1)") (class "Default")
      (node (ref "AIN_BNB") (pin "67") (pinfunction "67_67") (pintype "bidirectional"))
      (node (ref "AMP_A") (pin "1") (pinfunction "IN1_1") (pintype "input"))
    )
    (net (code "41") (name "Net-(AMP_A-IN2)") (class "Default")
      (node (ref "AIN_BNB") (pin "66") (pinfunction "66_66") (pintype "bidirectional"))
      (node (ref "AMP_A") (pin "2") (pinfunction "IN2_2") (pintype "input"))
    )
    (net (code "42") (name "Net-(AMP_A-IN3)") (class "Default")
      (node (ref "AIN_BNB") (pin "65") (pinfunction "65_65") (pintype "bidirectional"))
      (node (ref "AMP_A") (pin "3") (pinfunction "IN3_3") (pintype "input"))
    )
    (net (code "43") (name "Net-(AMP_A-IN4)") (class "Default")
      (node (ref "AIN_BNB") (pin "64") (pinfunction "64_64") (pintype "bidirectional"))
      (node (ref "AMP_A") (pin "4") (pinfunction "IN4_4") (pintype "input"))
    )
    (net (code "44") (name "Net-(AMP_A-IN5)") (class "Default")
      (node (ref "AIN_BNB") (pin "63") (pinfunction "63_63") (pintype "bidirectional"))
      (node (ref "AMP_A") (pin "5") (pinfunction "IN5_5") (pintype "input"))
    )
    (net (code "45") (name "Net-(AMP_A-IN6)") (class "Default")
      (node (ref "AIN_BNB") (pin "62") (pinfunction "62_62") (pintype "bidirectional"))
      (node (ref "AMP_A") (pin "6") (pinfunction "IN6_6") (pintype "input"))
    )
    (net (code "46") (name "Net-(AMP_A-IN7)") (class "Default")
      (node (ref "AIN_BNB") (pin "61") (pinfunction "61_61") (pintype "bidirectional"))
      (node (ref "AMP_A") (pin "7") (pinfunction "IN7_7") (pintype "input"))
    )
    (net (code "47") (name "Net-(AMP_A-IN8)") (class "Default")
      (node (ref "AIN_BNB") (pin "60") (pinfunction "60_60") (pintype "bidirectional"))
      (node (ref "AMP_A") (pin "8") (pinfunction "IN8_8") (pintype "input"))
    )
    (net (code "48") (name "Net-(AMP_A-IN9)") (class "Default")
      (node (ref "AIN_BNB") (pin "59") (pinfunction "59_59") (pintype "bidirectional"))
      (node (ref "AMP_A") (pin "9") (pinfunction "IN9_9") (pintype "input"))
    )
    (net (code "49") (name "Net-(AMP_A-IN10)") (class "Default")
      (node (ref "AIN_BNB") (pin "58") (pinfunction "58_58") (pintype "bidirectional"))
      (node (ref "AMP_A") (pin "10") (pinfunction "IN10_10") (pintype "input"))
    )
    (net (code "50") (name "Net-(AMP_A-IN11)") (class "Default")
      (node (ref "AIN_BNB") (pin "57") (pinfunction "57_57") (pintype "bidirectional"))
      (node (ref "AMP_A") (pin "11") (pinfunction "IN11_11") (pintype "input"))
    )
    (net (code "51") (name "Net-(AMP_A-IN12)") (class "Default")
      (node (ref "AIN_BNB") (pin "56") (pinfunction "56_56") (pintype "bidirectional"))
      (node (ref "AMP_A") (pin "12") (pinfunction "IN12_12") (pintype "input"))
    )
    (net (code "52") (name "Net-(AMP_A-IN13)") (class "Default")
      (node (ref "AIN_BNB") (pin "55") (pinfunction "55_55") (pintype "bidirectional"))
      (node (ref "AMP_A") (pin "13") (pinfunction "IN13_13") (pintype "input"))
    )
    (net (code "53") (name "Net-(AMP_A-IN14)") (class "Default")
      (node (ref "AIN_BNB") (pin "54") (pinfunction "54_54") (pintype "bidirectional"))
      (node (ref "AMP_A") (pin "14") (pinfunction "IN14_14") (pintype "input"))
    )
    (net (code "54") (name "Net-(AMP_A-IN15)") (class "Default")
      (node (ref "AIN_BNB") (pin "53") (pinfunction "53_53") (pintype "bidirectional"))
      (node (ref "AMP_A") (pin "15") (pinfunction "IN15_15") (pintype "input"))
    )
    (net (code "55") (name "Net-(AMP_A-IN16)") (class "Default")
      (node (ref "AIN_BNB") (pin "52") (pinfunction "52_52") (pintype "bidirectional"))
      (node (ref "AMP_A") (pin "16") (pinfunction "IN16_16") (pintype "input"))
    )
    (net (code "56") (name "Net-(AMP_A-IN17)") (class "Default")
      (node (ref "AIN_BNB") (pin "51") (pinfunction "51_51") (pintype "bidirectional"))
      (node (ref "AMP_A") (pin "17") (pinfunction "IN17_17") (pintype "input"))
    )
    (net (code "57") (name "Net-(AMP_A-IN18)") (class "Default")
      (node (ref "AIN_BNB") (pin "50") (pinfunction "50_50") (pintype "bidirectional"))
      (node (ref "AMP_A") (pin "18") (pinfunction "IN18_18") (pintype "input"))
    )
    (net (code "58") (name "Net-(AMP_A-IN19)") (class "Default")
      (node (ref "AIN_BNB") (pin "49") (pinfunction "49_49") (pintype "bidirectional"))
      (node (ref "AMP_A") (pin "19") (pinfunction "IN19_19") (pintype "input"))
    )
    (net (code "59") (name "Net-(AMP_A-IN20)") (class "Default")
      (node (ref "AIN_BNB") (pin "48") (pinfunction "48_48") (pintype "bidirectional"))
      (node (ref "AMP_A") (pin "20") (pinfunction "IN20_20") (pintype "input"))
    )
    (net (code "60") (name "Net-(AMP_A-IN21)") (class "Default")
      (node (ref "AIN_BNB") (pin "47") (pinfunction "47_47") (pintype "bidirectional"))
      (node (ref "AMP_A") (pin "21") (pinfunction "IN21_21") (pintype "input"))
    )
    (net (code "61") (name "Net-(AMP_A-IN22)") (class "Default")
      (node (ref "AIN_BNB") (pin "46") (pinfunction "46_46") (pintype "bidirectional"))
      (node (ref "AMP_A") (pin "22") (pinfunction "IN22_22") (pintype "input"))
    )
    (net (code "62") (name "Net-(AMP_A-IN23)") (class "Default")
      (node (ref "AIN_BNB") (pin "45") (pinfunction "45_45") (pintype "bidirectional"))
      (node (ref "AMP_A") (pin "23") (pinfunction "IN23_23") (pintype "input"))
    )
    (net (code "63") (name "Net-(AMP_A-IN24)") (class "Default")
      (node (ref "AIN_BNB") (pin "44") (pinfunction "44_44") (pintype "bidirectional"))
      (node (ref "AMP_A") (pin "24") (pinfunction "IN24_24") (pintype "input"))
    )
    (net (code "64") (name "Net-(AMP_A-IN25)") (class "Default")
      (node (ref "AIN_BNB") (pin "43") (pinfunction "43_43") (pintype "bidirectional"))
      (node (ref "AMP_A") (pin "25") (pinfunction "IN25_25") (pintype "input"))
    )
    (net (code "65") (name "Net-(AMP_A-IN26)") (class "Default")
      (node (ref "AIN_BNB") (pin "42") (pinfunction "42_42") (pintype "bidirectional"))
      (node (ref "AMP_A") (pin "26") (pinfunction "IN26_26") (pintype "input"))
    )
    (net (code "66") (name "Net-(AMP_A-IN27)") (class "Default")
      (node (ref "AIN_BNB") (pin "41") (pinfunction "41_41") (pintype "bidirectional"))
      (node (ref "AMP_A") (pin "27") (pinfunction "IN27_27") (pintype "input"))
    )
    (net (code "67") (name "Net-(AMP_A-IN28)") (class "Default")
      (node (ref "AIN_BNB") (pin "40") (pinfunction "40_40") (pintype "bidirectional"))
      (node (ref "AMP_A") (pin "28") (pinfunction "IN28_28") (pintype "input"))
    )
    (net (code "68") (name "Net-(AMP_A-IN29)") (class "Default")
      (node (ref "AIN_BNB") (pin "39") (pinfunction "39_39") (pintype "bidirectional"))
      (node (ref "AMP_A") (pin "29") (pinfunction "IN29_29") (pintype "input"))
    )
    (net (code "69") (name "Net-(AMP_A-IN30)") (class "Default")
      (node (ref "AIN_BNB") (pin "38") (pinfunction "38_38") (pintype "bidirectional"))
      (node (ref "AMP_A") (pin "30") (pinfunction "IN30_30") (pintype "input"))
    )
    (net (code "70") (name "Net-(AMP_A-IN31)") (class "Default")
      (node (ref "AIN_BNB") (pin "37") (pinfunction "37_37") (pintype "bidirectional"))
      (node (ref "AMP_A") (pin "31") (pinfunction "IN31_31") (pintype "input"))
    )
    (net (code "71") (name "Net-(AMP_A-IN32)") (class "Default")
      (node (ref "AIN_BNB") (pin "33") (pinfunction "33_33") (pintype "bidirectional"))
      (node (ref "AMP_A") (pin "32") (pinfunction "IN32_32") (pintype "input"))
    )
    (net (code "72") (name "Net-(AMP_A-IN33)") (class "Default")
      (node (ref "AIN_BNB") (pin "32") (pinfunction "32_32") (pintype "bidirectional"))
      (node (ref "AMP_A") (pin "33") (pinfunction "IN33_33") (pintype "input"))
    )
    (net (code "73") (name "Net-(AMP_A-IN34)") (class "Default")
      (node (ref "AIN_BNB") (pin "31") (pinfunction "31_31") (pintype "bidirectional"))
      (node (ref "AMP_A") (pin "34") (pinfunction "IN34_34") (pintype "input"))
    )
    (net (code "74") (name "Net-(AMP_A-IN35)") (class "Default")
      (node (ref "AIN_BNB") (pin "30") (pinfunction "30_30") (pintype "bidirectional"))
      (node (ref "AMP_A") (pin "35") (pinfunction "IN35_35") (pintype "input"))
    )
    (net (code "75") (name "Net-(AMP_A-IN36)") (class "Default")
      (node (ref "AIN_BNB") (pin "29") (pinfunction "29_29") (pintype "bidirectional"))
      (node (ref "AMP_A") (pin "36") (pinfunction "IN36_36") (pintype "input"))
    )
    (net (code "76") (name "Net-(AMP_A-IN37)") (class "Default")
      (node (ref "AIN_BNB") (pin "28") (pinfunction "28_28") (pintype "bidirectional"))
      (node (ref "AMP_A") (pin "37") (pinfunction "IN37_37") (pintype "input"))
    )
    (net (code "77") (name "Net-(AMP_A-IN38)") (class "Default")
      (node (ref "AIN_BNB") (pin "27") (pinfunction "27_27") (pintype "bidirectional"))
      (node (ref "AMP_A") (pin "38") (pinfunction "IN38_38") (pintype "input"))
    )
    (net (code "78") (name "Net-(AMP_A-IN39)") (class "Default")
      (node (ref "AIN_BNB") (pin "26") (pinfunction "26_26") (pintype "bidirectional"))
      (node (ref "AMP_A") (pin "39") (pinfunction "IN39_39") (pintype "input"))
    )
    (net (code "79") (name "Net-(AMP_A-IN40)") (class "Default")
      (node (ref "AIN_BNB") (pin "25") (pinfunction "25_25") (pintype "bidirectional"))
      (node (ref "AMP_A") (pin "40") (pinfunction "IN40_40") (pintype "input"))
    )
    (net (code "80") (name "Net-(AMP_A-IN41)") (class "Default")
      (node (ref "AIN_BNB") (pin "24") (pinfunction "24_24") (pintype "bidirectional"))
      (node (ref "AMP_A") (pin "41") (pinfunction "IN41_41") (pintype "input"))
    )
    (net (code "81") (name "Net-(AMP_A-IN42)") (class "Default")
      (node (ref "AIN_BNB") (pin "23") (pinfunction "23_23") (pintype "bidirectional"))
      (node (ref "AMP_A") (pin "42") (pinfunction "IN42_42") (pintype "input"))
    )
    (net (code "82") (name "Net-(AMP_A-IN43)") (class "Default")
      (node (ref "AIN_BNB") (pin "22") (pinfunction "22_22") (pintype "bidirectional"))
      (node (ref "AMP_A") (pin "43") (pinfunction "IN43_43") (pintype "input"))
    )
    (net (code "83") (name "Net-(AMP_A-IN44)") (class "Default")
      (node (ref "AIN_BNB") (pin "21") (pinfunction "21_21") (pintype "bidirectional"))
      (node (ref "AMP_A") (pin "44") (pinfunction "IN44_44") (pintype "input"))
    )
    (net (code "84") (name "Net-(AMP_A-IN45)") (class "Default")
      (node (ref "AIN_BNB") (pin "20") (pinfunction "20_20") (pintype "bidirectional"))
      (node (ref "AMP_A") (pin "45") (pinfunction "IN45_45") (pintype "input"))
    )
    (net (code "85") (name "Net-(AMP_A-IN46)") (class "Default")
      (node (ref "AIN_BNB") (pin "19") (pinfunction "19_19") (pintype "bidirectional"))
      (node (ref "AMP_A") (pin "46") (pinfunction "IN46_46") (pintype "input"))
    )
    (net (code "86") (name "Net-(AMP_A-IN47)") (class "Default")
      (node (ref "AIN_BNB") (pin "18") (pinfunction "18_18") (pintype "bidirectional"))
      (node (ref "AMP_A") (pin "47") (pinfunction "IN47_47") (pintype "input"))
    )
    (net (code "87") (name "Net-(AMP_A-IN48)") (class "Default")
      (node (ref "AIN_BNB") (pin "17") (pinfunction "17_17") (pintype "bidirectional"))
      (node (ref "AMP_A") (pin "48") (pinfunction "IN48_48") (pintype "input"))
    )
    (net (code "88") (name "Net-(AMP_A-IN49)") (class "Default")
      (node (ref "AIN_BNB") (pin "16") (pinfunction "16_16") (pintype "bidirectional"))
      (node (ref "AMP_A") (pin "49") (pinfunction "IN49_49") (pintype "input"))
    )
    (net (code "89") (name "Net-(AMP_A-IN50)") (class "Default")
      (node (ref "AIN_BNB") (pin "15") (pinfunction "15_15") (pintype "bidirectional"))
      (node (ref "AMP_A") (pin "50") (pinfunction "IN50_50") (pintype "input"))
    )
    (net (code "90") (name "Net-(AMP_A-IN51)") (class "Default")
      (node (ref "AIN_BNB") (pin "14") (pinfunction "14_14") (pintype "bidirectional"))
      (node (ref "AMP_A") (pin "51") (pinfunction "IN51_51") (pintype "input"))
    )
    (net (code "91") (name "Net-(AMP_A-IN52)") (class "Default")
      (node (ref "AIN_BNB") (pin "13") (pinfunction "13_13") (pintype "bidirectional"))
      (node (ref "AMP_A") (pin "52") (pinfunction "IN52_52") (pintype "input"))
    )
    (net (code "92") (name "Net-(AMP_A-IN53)") (class "Default")
      (node (ref "AIN_BNB") (pin "12") (pinfunction "12_12") (pintype "bidirectional"))
      (node (ref "AMP_A") (pin "53") (pinfunction "IN53_53") (pintype "input"))
    )
    (net (code "93") (name "Net-(AMP_A-IN54)") (class "Default")
      (node (ref "AIN_BNB") (pin "11") (pinfunction "11_11") (pintype "bidirectional"))
      (node (ref "AMP_A") (pin "54") (pinfunction "IN54_54") (pintype "input"))
    )
    (net (code "94") (name "Net-(AMP_A-IN55)") (class "Default")
      (node (ref "AIN_BNB") (pin "10") (pinfunction "10_10") (pintype "bidirectional"))
      (node (ref "AMP_A") (pin "55") (pinfunction "IN55_55") (pintype "input"))
    )
    (net (code "95") (name "Net-(AMP_A-IN56)") (class "Default")
      (node (ref "AIN_BNB") (pin "9") (pinfunction "9_9") (pintype "bidirectional"))
      (node (ref "AMP_A") (pin "56") (pinfunction "IN56_56") (pintype "input"))
    )
    (net (code "96") (name "Net-(AMP_A-IN57)") (class "Default")
      (node (ref "AIN_BNB") (pin "8") (pinfunction "8_8") (pintype "bidirectional"))
      (node (ref "AMP_A") (pin "57") (pinfunction "IN57_57") (pintype "input"))
    )
    (net (code "97") (name "Net-(AMP_A-IN58)") (class "Default")
      (node (ref "AIN_BNB") (pin "7") (pinfunction "7_7") (pintype "bidirectional"))
      (node (ref "AMP_A") (pin "58") (pinfunction "IN58_58") (pintype "input"))
    )
    (net (code "98") (name "Net-(AMP_A-IN59)") (class "Default")
      (node (ref "AIN_BNB") (pin "6") (pinfunction "6_6") (pintype "bidirectional"))
      (node (ref "AMP_A") (pin "59") (pinfunction "IN59_59") (pintype "input"))
    )
    (net (code "99") (name "Net-(AMP_A-IN60)") (class "Default")
      (node (ref "AIN_BNB") (pin "5") (pinfunction "5_5") (pintype "bidirectional"))
      (node (ref "AMP_A") (pin "60") (pinfunction "IN60_60") (pintype "input"))
    )
    (net (code "100") (name "Net-(AMP_A-IN61)") (class "Default")
      (node (ref "AIN_BNB") (pin "4") (pinfunction "4_4") (pintype "bidirectional"))
      (node (ref "AMP_A") (pin "61") (pinfunction "IN61_61") (pintype "input"))
    )
    (net (code "101") (name "Net-(AMP_A-IN62)") (class "Default")
      (node (ref "AIN_BNB") (pin "3") (pinfunction "3_3") (pintype "bidirectional"))
      (node (ref "AMP_A") (pin "62") (pinfunction "IN62_62") (pintype "input"))
    )
    (net (code "102") (name "Net-(AMP_A-IN63)") (class "Default")
      (node (ref "AIN_BNB") (pin "2") (pinfunction "2_2") (pintype "bidirectional"))
      (node (ref "AMP_A") (pin "63") (pinfunction "IN63_63") (pintype "input"))
    )
    (net (code "103") (name "Net-(AMP_B-ADC_REF)") (class "Default")
      (node (ref "AMP_B") (pin "B19") (pinfunction "ADC_REF_B19") (pintype "passive"))
      (node (ref "C7") (pin "1") (pinfunction "1_1") (pintype "passive"))
    )
    (net (code "104") (name "Net-(AMP_B-AUXIN1)") (class "Default")
      (node (ref "AMP_B") (pin "B5") (pinfunction "AUXIN1_B5") (pintype "input"))
      (node (ref "C4") (pin "2") (pinfunction "2_2") (pintype "passive"))
      (node (ref "U1") (pin "XOUT") (pinfunction "XOUT_XOUT") (pintype "bidirectional"))
    )
    (net (code "105") (name "Net-(AMP_B-AUXIN2)") (class "Default")
      (node (ref "AMP_B") (pin "B6") (pinfunction "AUXIN2_B6") (pintype "input"))
      (node (ref "C5") (pin "2") (pinfunction "2_2") (pintype "passive"))
      (node (ref "U1") (pin "YOUT") (pinfunction "YOUT_YOUT") (pintype "bidirectional"))
    )
    (net (code "106") (name "Net-(AMP_B-AUXIN3)") (class "Default")
      (node (ref "AMP_B") (pin "B7") (pinfunction "AUXIN3_B7") (pintype "input"))
      (node (ref "C6") (pin "2") (pinfunction "2_2") (pintype "passive"))
      (node (ref "U1") (pin "ZOUT") (pinfunction "ZOUT_ZOUT") (pintype "bidirectional"))
    )
    (net (code "107") (name "Net-(AMP_B-IN0)") (class "Default")
      (node (ref "AIN_BSB") (pin "68") (pinfunction "68_68") (pintype "bidirectional"))
      (node (ref "AMP_B") (pin "0") (pinfunction "IN0_0") (pintype "input"))
    )
    (net (code "108") (name "Net-(AMP_B-IN1)") (class "Default")
      (node (ref "AIN_BSB") (pin "67") (pinfunction "67_67") (pintype "bidirectional"))
      (node (ref "AMP_B") (pin "1") (pinfunction "IN1_1") (pintype "input"))
    )
    (net (code "109") (name "Net-(AMP_B-IN2)") (class "Default")
      (node (ref "AIN_BSB") (pin "66") (pinfunction "66_66") (pintype "bidirectional"))
      (node (ref "AMP_B") (pin "2") (pinfunction "IN2_2") (pintype "input"))
    )
    (net (code "110") (name "Net-(AMP_B-IN3)") (class "Default")
      (node (ref "AIN_BSB") (pin "65") (pinfunction "65_65") (pintype "bidirectional"))
      (node (ref "AMP_B") (pin "3") (pinfunction "IN3_3") (pintype "input"))
    )
    (net (code "111") (name "Net-(AMP_B-IN4)") (class "Default")
      (node (ref "AIN_BSB") (pin "64") (pinfunction "64_64") (pintype "bidirectional"))
      (node (ref "AMP_B") (pin "4") (pinfunction "IN4_4") (pintype "input"))
    )
    (net (code "112") (name "Net-(AMP_B-IN5)") (class "Default")
      (node (ref "AIN_BSB") (pin "63") (pinfunction "63_63") (pintype "bidirectional"))
      (node (ref "AMP_B") (pin "5") (pinfunction "IN5_5") (pintype "input"))
    )
    (net (code "113") (name "Net-(AMP_B-IN6)") (class "Default")
      (node (ref "AIN_BSB") (pin "62") (pinfunction "62_62") (pintype "bidirectional"))
      (node (ref "AMP_B") (pin "6") (pinfunction "IN6_6") (pintype "input"))
    )
    (net (code "114") (name "Net-(AMP_B-IN7)") (class "Default")
      (node (ref "AIN_BSB") (pin "61") (pinfunction "61_61") (pintype "bidirectional"))
      (node (ref "AMP_B") (pin "7") (pinfunction "IN7_7") (pintype "input"))
    )
    (net (code "115") (name "Net-(AMP_B-IN8)") (class "Default")
      (node (ref "AIN_BSB") (pin "60") (pinfunction "60_60") (pintype "bidirectional"))
      (node (ref "AMP_B") (pin "8") (pinfunction "IN8_8") (pintype "input"))
    )
    (net (code "116") (name "Net-(AMP_B-IN9)") (class "Default")
      (node (ref "AIN_BSB") (pin "59") (pinfunction "59_59") (pintype "bidirectional"))
      (node (ref "AMP_B") (pin "9") (pinfunction "IN9_9") (pintype "input"))
    )
    (net (code "117") (name "Net-(AMP_B-IN10)") (class "Default")
      (node (ref "AIN_BSB") (pin "58") (pinfunction "58_58") (pintype "bidirectional"))
      (node (ref "AMP_B") (pin "10") (pinfunction "IN10_10") (pintype "input"))
    )
    (net (code "118") (name "Net-(AMP_B-IN11)") (class "Default")
      (node (ref "AIN_BSB") (pin "57") (pinfunction "57_57") (pintype "bidirectional"))
      (node (ref "AMP_B") (pin "11") (pinfunction "IN11_11") (pintype "input"))
    )
    (net (code "119") (name "Net-(AMP_B-IN12)") (class "Default")
      (node (ref "AIN_BSB") (pin "56") (pinfunction "56_56") (pintype "bidirectional"))
      (node (ref "AMP_B") (pin "12") (pinfunction "IN12_12") (pintype "input"))
    )
    (net (code "120") (name "Net-(AMP_B-IN13)") (class "Default")
      (node (ref "AIN_BSB") (pin "55") (pinfunction "55_55") (pintype "bidirectional"))
      (node (ref "AMP_B") (pin "13") (pinfunction "IN13_13") (pintype "input"))
    )
    (net (code "121") (name "Net-(AMP_B-IN14)") (class "Default")
      (node (ref "AIN_BSB") (pin "54") (pinfunction "54_54") (pintype "bidirectional"))
      (node (ref "AMP_B") (pin "14") (pinfunction "IN14_14") (pintype "input"))
    )
    (net (code "122") (name "Net-(AMP_B-IN15)") (class "Default")
      (node (ref "AIN_BSB") (pin "53") (pinfunction "53_53") (pintype "bidirectional"))
      (node (ref "AMP_B") (pin "15") (pinfunction "IN15_15") (pintype "input"))
    )
    (net (code "123") (name "Net-(AMP_B-IN16)") (class "Default")
      (node (ref "AIN_BSB") (pin "52") (pinfunction "52_52") (pintype "bidirectional"))
      (node (ref "AMP_B") (pin "16") (pinfunction "IN16_16") (pintype "input"))
    )
    (net (code "124") (name "Net-(AMP_B-IN17)") (class "Default")
      (node (ref "AIN_BSB") (pin "51") (pinfunction "51_51") (pintype "bidirectional"))
      (node (ref "AMP_B") (pin "17") (pinfunction "IN17_17") (pintype "input"))
    )
    (net (code "125") (name "Net-(AMP_B-IN18)") (class "Default")
      (node (ref "AIN_BSB") (pin "50") (pinfunction "50_50") (pintype "bidirectional"))
      (node (ref "AMP_B") (pin "18") (pinfunction "IN18_18") (pintype "input"))
    )
    (net (code "126") (name "Net-(AMP_B-IN19)") (class "Default")
      (node (ref "AIN_BSB") (pin "49") (pinfunction "49_49") (pintype "bidirectional"))
      (node (ref "AMP_B") (pin "19") (pinfunction "IN19_19") (pintype "input"))
    )
    (net (code "127") (name "Net-(AMP_B-IN20)") (class "Default")
      (node (ref "AIN_BSB") (pin "48") (pinfunction "48_48") (pintype "bidirectional"))
      (node (ref "AMP_B") (pin "20") (pinfunction "IN20_20") (pintype "input"))
    )
    (net (code "128") (name "Net-(AMP_B-IN21)") (class "Default")
      (node (ref "AIN_BSB") (pin "47") (pinfunction "47_47") (pintype "bidirectional"))
      (node (ref "AMP_B") (pin "21") (pinfunction "IN21_21") (pintype "input"))
    )
    (net (code "129") (name "Net-(AMP_B-IN22)") (class "Default")
      (node (ref "AIN_BSB") (pin "46") (pinfunction "46_46") (pintype "bidirectional"))
      (node (ref "AMP_B") (pin "22") (pinfunction "IN22_22") (pintype "input"))
    )
    (net (code "130") (name "Net-(AMP_B-IN23)") (class "Default")
      (node (ref "AIN_BSB") (pin "45") (pinfunction "45_45") (pintype "bidirectional"))
      (node (ref "AMP_B") (pin "23") (pinfunction "IN23_23") (pintype "input"))
    )
    (net (code "131") (name "Net-(AMP_B-IN24)") (class "Default")
      (node (ref "AIN_BSB") (pin "44") (pinfunction "44_44") (pintype "bidirectional"))
      (node (ref "AMP_B") (pin "24") (pinfunction "IN24_24") (pintype "input"))
    )
    (net (code "132") (name "Net-(AMP_B-IN25)") (class "Default")
      (node (ref "AIN_BSB") (pin "43") (pinfunction "43_43") (pintype "bidirectional"))
      (node (ref "AMP_B") (pin "25") (pinfunction "IN25_25") (pintype "input"))
    )
    (net (code "133") (name "Net-(AMP_B-IN26)") (class "Default")
      (node (ref "AIN_BSB") (pin "42") (pinfunction "42_42") (pintype "bidirectional"))
      (node (ref "AMP_B") (pin "26") (pinfunction "IN26_26") (pintype "input"))
    )
    (net (code "134") (name "Net-(AMP_B-IN27)") (class "Default")
      (node (ref "AIN_BSB") (pin "41") (pinfunction "41_41") (pintype "bidirectional"))
      (node (ref "AMP_B") (pin "27") (pinfunction "IN27_27") (pintype "input"))
    )
    (net (code "135") (name "Net-(AMP_B-IN28)") (class "Default")
      (node (ref "AIN_BSB") (pin "40") (pinfunction "40_40") (pintype "bidirectional"))
      (node (ref "AMP_B") (pin "28") (pinfunction "IN28_28") (pintype "input"))
    )
    (net (code "136") (name "Net-(AMP_B-IN29)") (class "Default")
      (node (ref "AIN_BSB") (pin "39") (pinfunction "39_39") (pintype "bidirectional"))
      (node (ref "AMP_B") (pin "29") (pinfunction "IN29_29") (pintype "input"))
    )
    (net (code "137") (name "Net-(AMP_B-IN30)") (class "Default")
      (node (ref "AIN_BSB") (pin "38") (pinfunction "38_38") (pintype "bidirectional"))
      (node (ref "AMP_B") (pin "30") (pinfunction "IN30_30") (pintype "input"))
    )
    (net (code "138") (name "Net-(AMP_B-IN31)") (class "Default")
      (node (ref "AIN_BSB") (pin "37") (pinfunction "37_37") (pintype "bidirectional"))
      (node (ref "AMP_B") (pin "31") (pinfunction "IN31_31") (pintype "input"))
    )
    (net (code "139") (name "Net-(AMP_B-IN32)") (class "Default")
      (node (ref "AIN_BSB") (pin "33") (pinfunction "33_33") (pintype "bidirectional"))
      (node (ref "AMP_B") (pin "32") (pinfunction "IN32_32") (pintype "input"))
    )
    (net (code "140") (name "Net-(AMP_B-IN33)") (class "Default")
      (node (ref "AIN_BSB") (pin "32") (pinfunction "32_32") (pintype "bidirectional"))
      (node (ref "AMP_B") (pin "33") (pinfunction "IN33_33") (pintype "input"))
    )
    (net (code "141") (name "Net-(AMP_B-IN34)") (class "Default")
      (node (ref "AIN_BSB") (pin "31") (pinfunction "31_31") (pintype "bidirectional"))
      (node (ref "AMP_B") (pin "34") (pinfunction "IN34_34") (pintype "input"))
    )
    (net (code "142") (name "Net-(AMP_B-IN35)") (class "Default")
      (node (ref "AIN_BSB") (pin "30") (pinfunction "30_30") (pintype "bidirectional"))
      (node (ref "AMP_B") (pin "35") (pinfunction "IN35_35") (pintype "input"))
    )
    (net (code "143") (name "Net-(AMP_B-IN36)") (class "Default")
      (node (ref "AIN_BSB") (pin "29") (pinfunction "29_29") (pintype "bidirectional"))
      (node (ref "AMP_B") (pin "36") (pinfunction "IN36_36") (pintype "input"))
    )
    (net (code "144") (name "Net-(AMP_B-IN37)") (class "Default")
      (node (ref "AIN_BSB") (pin "28") (pinfunction "28_28") (pintype "bidirectional"))
      (node (ref "AMP_B") (pin "37") (pinfunction "IN37_37") (pintype "input"))
    )
    (net (code "145") (name "Net-(AMP_B-IN38)") (class "Default")
      (node (ref "AIN_BSB") (pin "27") (pinfunction "27_27") (pintype "bidirectional"))
      (node (ref "AMP_B") (pin "38") (pinfunction "IN38_38") (pintype "input"))
    )
    (net (code "146") (name "Net-(AMP_B-IN39)") (class "Default")
      (node (ref "AIN_BSB") (pin "26") (pinfunction "26_26") (pintype "bidirectional"))
      (node (ref "AMP_B") (pin "39") (pinfunction "IN39_39") (pintype "input"))
    )
    (net (code "147") (name "Net-(AMP_B-IN40)") (class "Default")
      (node (ref "AIN_BSB") (pin "25") (pinfunction "25_25") (pintype "bidirectional"))
      (node (ref "AMP_B") (pin "40") (pinfunction "IN40_40") (pintype "input"))
    )
    (net (code "148") (name "Net-(AMP_B-IN41)") (class "Default")
      (node (ref "AIN_BSB") (pin "24") (pinfunction "24_24") (pintype "bidirectional"))
      (node (ref "AMP_B") (pin "41") (pinfunction "IN41_41") (pintype "input"))
    )
    (net (code "149") (name "Net-(AMP_B-IN42)") (class "Default")
      (node (ref "AIN_BSB") (pin "23") (pinfunction "23_23") (pintype "bidirectional"))
      (node (ref "AMP_B") (pin "42") (pinfunction "IN42_42") (pintype "input"))
    )
    (net (code "150") (name "Net-(AMP_B-IN43)") (class "Default")
      (node (ref "AIN_BSB") (pin "22") (pinfunction "22_22") (pintype "bidirectional"))
      (node (ref "AMP_B") (pin "43") (pinfunction "IN43_43") (pintype "input"))
    )
    (net (code "151") (name "Net-(AMP_B-IN44)") (class "Default")
      (node (ref "AIN_BSB") (pin "21") (pinfunction "21_21") (pintype "bidirectional"))
      (node (ref "AMP_B") (pin "44") (pinfunction "IN44_44") (pintype "input"))
    )
    (net (code "152") (name "Net-(AMP_B-IN45)") (class "Default")
      (node (ref "AIN_BSB") (pin "20") (pinfunction "20_20") (pintype "bidirectional"))
      (node (ref "AMP_B") (pin "45") (pinfunction "IN45_45") (pintype "input"))
    )
    (net (code "153") (name "Net-(AMP_B-IN46)") (class "Default")
      (node (ref "AIN_BSB") (pin "19") (pinfunction "19_19") (pintype "bidirectional"))
      (node (ref "AMP_B") (pin "46") (pinfunction "IN46_46") (pintype "input"))
    )
    (net (code "154") (name "Net-(AMP_B-IN47)") (class "Default")
      (node (ref "AIN_BSB") (pin "18") (pinfunction "18_18") (pintype "bidirectional"))
      (node (ref "AMP_B") (pin "47") (pinfunction "IN47_47") (pintype "input"))
    )
    (net (code "155") (name "Net-(AMP_B-IN48)") (class "Default")
      (node (ref "AIN_BSB") (pin "17") (pinfunction "17_17") (pintype "bidirectional"))
      (node (ref "AMP_B") (pin "48") (pinfunction "IN48_48") (pintype "input"))
    )
    (net (code "156") (name "Net-(AMP_B-IN49)") (class "Default")
      (node (ref "AIN_BSB") (pin "16") (pinfunction "16_16") (pintype "bidirectional"))
      (node (ref "AMP_B") (pin "49") (pinfunction "IN49_49") (pintype "input"))
    )
    (net (code "157") (name "Net-(AMP_B-IN50)") (class "Default")
      (node (ref "AIN_BSB") (pin "15") (pinfunction "15_15") (pintype "bidirectional"))
      (node (ref "AMP_B") (pin "50") (pinfunction "IN50_50") (pintype "input"))
    )
    (net (code "158") (name "Net-(AMP_B-IN51)") (class "Default")
      (node (ref "AIN_BSB") (pin "14") (pinfunction "14_14") (pintype "bidirectional"))
      (node (ref "AMP_B") (pin "51") (pinfunction "IN51_51") (pintype "input"))
    )
    (net (code "159") (name "Net-(AMP_B-IN52)") (class "Default")
      (node (ref "AIN_BSB") (pin "13") (pinfunction "13_13") (pintype "bidirectional"))
      (node (ref "AMP_B") (pin "52") (pinfunction "IN52_52") (pintype "input"))
    )
    (net (code "160") (name "Net-(AMP_B-IN53)") (class "Default")
      (node (ref "AIN_BSB") (pin "12") (pinfunction "12_12") (pintype "bidirectional"))
      (node (ref "AMP_B") (pin "53") (pinfunction "IN53_53") (pintype "input"))
    )
    (net (code "161") (name "Net-(AMP_B-IN54)") (class "Default")
      (node (ref "AIN_BSB") (pin "11") (pinfunction "11_11") (pintype "bidirectional"))
      (node (ref "AMP_B") (pin "54") (pinfunction "IN54_54") (pintype "input"))
    )
    (net (code "162") (name "Net-(AMP_B-IN55)") (class "Default")
      (node (ref "AIN_BSB") (pin "10") (pinfunction "10_10") (pintype "bidirectional"))
      (node (ref "AMP_B") (pin "55") (pinfunction "IN55_55") (pintype "input"))
    )
    (net (code "163") (name "Net-(AMP_B-IN56)") (class "Default")
      (node (ref "AIN_BSB") (pin "9") (pinfunction "9_9") (pintype "bidirectional"))
      (node (ref "AMP_B") (pin "56") (pinfunction "IN56_56") (pintype "input"))
    )
    (net (code "164") (name "Net-(AMP_B-IN57)") (class "Default")
      (node (ref "AIN_BSB") (pin "8") (pinfunction "8_8") (pintype "bidirectional"))
      (node (ref "AMP_B") (pin "57") (pinfunction "IN57_57") (pintype "input"))
    )
    (net (code "165") (name "Net-(AMP_B-IN58)") (class "Default")
      (node (ref "AIN_BSB") (pin "7") (pinfunction "7_7") (pintype "bidirectional"))
      (node (ref "AMP_B") (pin "58") (pinfunction "IN58_58") (pintype "input"))
    )
    (net (code "166") (name "Net-(AMP_B-IN59)") (class "Default")
      (node (ref "AIN_BSB") (pin "6") (pinfunction "6_6") (pintype "bidirectional"))
      (node (ref "AMP_B") (pin "59") (pinfunction "IN59_59") (pintype "input"))
    )
    (net (code "167") (name "Net-(AMP_B-IN60)") (class "Default")
      (node (ref "AIN_BSB") (pin "5") (pinfunction "5_5") (pintype "bidirectional"))
      (node (ref "AMP_B") (pin "60") (pinfunction "IN60_60") (pintype "input"))
    )
    (net (code "168") (name "Net-(AMP_B-IN61)") (class "Default")
      (node (ref "AIN_BSB") (pin "4") (pinfunction "4_4") (pintype "bidirectional"))
      (node (ref "AMP_B") (pin "61") (pinfunction "IN61_61") (pintype "input"))
    )
    (net (code "169") (name "Net-(AMP_B-IN62)") (class "Default")
      (node (ref "AIN_BSB") (pin "3") (pinfunction "3_3") (pintype "bidirectional"))
      (node (ref "AMP_B") (pin "62") (pinfunction "IN62_62") (pintype "input"))
    )
    (net (code "170") (name "Net-(AMP_B-IN63)") (class "Default")
      (node (ref "AIN_BSB") (pin "2") (pinfunction "2_2") (pintype "bidirectional"))
      (node (ref "AMP_B") (pin "63") (pinfunction "IN63_63") (pintype "input"))
    )
    (net (code "171") (name "Net-(ATHRU_BEB-Pad2)") (class "Default")
      (node (ref "ATHRU_BEB") (pin "2") (pinfunction "2_2") (pintype "bidirectional"))
      (node (ref "ATHRU_TEB") (pin "2") (pinfunction "2_2") (pintype "bidirectional"))
    )
    (net (code "172") (name "Net-(ATHRU_BEB-Pad3)") (class "Default")
      (node (ref "ATHRU_BEB") (pin "3") (pinfunction "3_3") (pintype "bidirectional"))
      (node (ref "ATHRU_TEB") (pin "3") (pinfunction "3_3") (pintype "bidirectional"))
    )
    (net (code "173") (name "Net-(ATHRU_BEB-Pad4)") (class "Default")
      (node (ref "ATHRU_BEB") (pin "4") (pinfunction "4_4") (pintype "bidirectional"))
      (node (ref "ATHRU_TEB") (pin "4") (pinfunction "4_4") (pintype "bidirectional"))
    )
    (net (code "174") (name "Net-(ATHRU_BEB-Pad5)") (class "Default")
      (node (ref "ATHRU_BEB") (pin "5") (pinfunction "5_5") (pintype "bidirectional"))
      (node (ref "ATHRU_TEB") (pin "5") (pinfunction "5_5") (pintype "bidirectional"))
    )
    (net (code "175") (name "Net-(ATHRU_BEB-Pad6)") (class "Default")
      (node (ref "ATHRU_BEB") (pin "6") (pinfunction "6_6") (pintype "bidirectional"))
      (node (ref "ATHRU_TEB") (pin "6") (pinfunction "6_6") (pintype "bidirectional"))
    )
    (net (code "176") (name "Net-(ATHRU_BEB-Pad7)") (class "Default")
      (node (ref "ATHRU_BEB") (pin "7") (pinfunction "7_7") (pintype "bidirectional"))
      (node (ref "ATHRU_TEB") (pin "7") (pinfunction "7_7") (pintype "bidirectional"))
    )
    (net (code "177") (name "Net-(ATHRU_BEB-Pad8)") (class "Default")
      (node (ref "ATHRU_BEB") (pin "8") (pinfunction "8_8") (pintype "bidirectional"))
      (node (ref "ATHRU_TEB") (pin "8") (pinfunction "8_8") (pintype "bidirectional"))
    )
    (net (code "178") (name "Net-(ATHRU_BEB-Pad9)") (class "Default")
      (node (ref "ATHRU_BEB") (pin "9") (pinfunction "9_9") (pintype "bidirectional"))
      (node (ref "ATHRU_TEB") (pin "9") (pinfunction "9_9") (pintype "bidirectional"))
    )
    (net (code "179") (name "Net-(ATHRU_BEB-Pad10)") (class "Default")
      (node (ref "ATHRU_BEB") (pin "10") (pinfunction "10_10") (pintype "bidirectional"))
      (node (ref "ATHRU_TEB") (pin "10") (pinfunction "10_10") (pintype "bidirectional"))
    )
    (net (code "180") (name "Net-(ATHRU_BEB-Pad11)") (class "Default")
      (node (ref "ATHRU_BEB") (pin "11") (pinfunction "11_11") (pintype "bidirectional"))
      (node (ref "ATHRU_TEB") (pin "11") (pinfunction "11_11") (pintype "bidirectional"))
    )
    (net (code "181") (name "Net-(ATHRU_BEB-Pad12)") (class "Default")
      (node (ref "ATHRU_BEB") (pin "12") (pinfunction "12_12") (pintype "bidirectional"))
      (node (ref "ATHRU_TEB") (pin "12") (pinfunction "12_12") (pintype "bidirectional"))
    )
    (net (code "182") (name "Net-(ATHRU_BEB-Pad13)") (class "Default")
      (node (ref "ATHRU_BEB") (pin "13") (pinfunction "13_13") (pintype "bidirectional"))
      (node (ref "ATHRU_TEB") (pin "13") (pinfunction "13_13") (pintype "bidirectional"))
    )
    (net (code "183") (name "Net-(ATHRU_BEB-Pad14)") (class "Default")
      (node (ref "ATHRU_BEB") (pin "14") (pinfunction "14_14") (pintype "bidirectional"))
      (node (ref "ATHRU_TEB") (pin "14") (pinfunction "14_14") (pintype "bidirectional"))
    )
    (net (code "184") (name "Net-(ATHRU_BEB-Pad15)") (class "Default")
      (node (ref "ATHRU_BEB") (pin "15") (pinfunction "15_15") (pintype "bidirectional"))
      (node (ref "ATHRU_TEB") (pin "15") (pinfunction "15_15") (pintype "bidirectional"))
    )
    (net (code "185") (name "Net-(ATHRU_BEB-Pad16)") (class "Default")
      (node (ref "ATHRU_BEB") (pin "16") (pinfunction "16_16") (pintype "bidirectional"))
      (node (ref "ATHRU_TEB") (pin "16") (pinfunction "16_16") (pintype "bidirectional"))
    )
    (net (code "186") (name "Net-(ATHRU_BEB-Pad17)") (class "Default")
      (node (ref "ATHRU_BEB") (pin "17") (pinfunction "17_17") (pintype "bidirectional"))
      (node (ref "ATHRU_TEB") (pin "17") (pinfunction "17_17") (pintype "bidirectional"))
    )
    (net (code "187") (name "Net-(ATHRU_BEB-Pad18)") (class "Default")
      (node (ref "ATHRU_BEB") (pin "18") (pinfunction "18_18") (pintype "bidirectional"))
      (node (ref "ATHRU_TEB") (pin "18") (pinfunction "18_18") (pintype "bidirectional"))
    )
    (net (code "188") (name "Net-(ATHRU_BEB-Pad19)") (class "Default")
      (node (ref "ATHRU_BEB") (pin "19") (pinfunction "19_19") (pintype "bidirectional"))
      (node (ref "ATHRU_TEB") (pin "19") (pinfunction "19_19") (pintype "bidirectional"))
    )
    (net (code "189") (name "Net-(ATHRU_BEB-Pad20)") (class "Default")
      (node (ref "ATHRU_BEB") (pin "20") (pinfunction "20_20") (pintype "bidirectional"))
      (node (ref "ATHRU_TEB") (pin "20") (pinfunction "20_20") (pintype "bidirectional"))
    )
    (net (code "190") (name "Net-(ATHRU_BEB-Pad21)") (class "Default")
      (node (ref "ATHRU_BEB") (pin "21") (pinfunction "21_21") (pintype "bidirectional"))
      (node (ref "ATHRU_TEB") (pin "21") (pinfunction "21_21") (pintype "bidirectional"))
    )
    (net (code "191") (name "Net-(ATHRU_BEB-Pad22)") (class "Default")
      (node (ref "ATHRU_BEB") (pin "22") (pinfunction "22_22") (pintype "bidirectional"))
      (node (ref "ATHRU_TEB") (pin "22") (pinfunction "22_22") (pintype "bidirectional"))
    )
    (net (code "192") (name "Net-(ATHRU_BEB-Pad23)") (class "Default")
      (node (ref "ATHRU_BEB") (pin "23") (pinfunction "23_23") (pintype "bidirectional"))
      (node (ref "ATHRU_TEB") (pin "23") (pinfunction "23_23") (pintype "bidirectional"))
    )
    (net (code "193") (name "Net-(ATHRU_BEB-Pad24)") (class "Default")
      (node (ref "ATHRU_BEB") (pin "24") (pinfunction "24_24") (pintype "bidirectional"))
      (node (ref "ATHRU_TEB") (pin "24") (pinfunction "24_24") (pintype "bidirectional"))
    )
    (net (code "194") (name "Net-(ATHRU_BEB-Pad25)") (class "Default")
      (node (ref "ATHRU_BEB") (pin "25") (pinfunction "25_25") (pintype "bidirectional"))
      (node (ref "ATHRU_TEB") (pin "25") (pinfunction "25_25") (pintype "bidirectional"))
    )
    (net (code "195") (name "Net-(ATHRU_BEB-Pad26)") (class "Default")
      (node (ref "ATHRU_BEB") (pin "26") (pinfunction "26_26") (pintype "bidirectional"))
      (node (ref "ATHRU_TEB") (pin "26") (pinfunction "26_26") (pintype "bidirectional"))
    )
    (net (code "196") (name "Net-(ATHRU_BEB-Pad27)") (class "Default")
      (node (ref "ATHRU_BEB") (pin "27") (pinfunction "27_27") (pintype "bidirectional"))
      (node (ref "ATHRU_TEB") (pin "27") (pinfunction "27_27") (pintype "bidirectional"))
    )
    (net (code "197") (name "Net-(ATHRU_BEB-Pad28)") (class "Default")
      (node (ref "ATHRU_BEB") (pin "28") (pinfunction "28_28") (pintype "bidirectional"))
      (node (ref "ATHRU_TEB") (pin "28") (pinfunction "28_28") (pintype "bidirectional"))
    )
    (net (code "198") (name "Net-(ATHRU_BEB-Pad29)") (class "Default")
      (node (ref "ATHRU_BEB") (pin "29") (pinfunction "29_29") (pintype "bidirectional"))
      (node (ref "ATHRU_TEB") (pin "29") (pinfunction "29_29") (pintype "bidirectional"))
    )
    (net (code "199") (name "Net-(ATHRU_BEB-Pad30)") (class "Default")
      (node (ref "ATHRU_BEB") (pin "30") (pinfunction "30_30") (pintype "bidirectional"))
      (node (ref "ATHRU_TEB") (pin "30") (pinfunction "30_30") (pintype "bidirectional"))
    )
    (net (code "200") (name "Net-(ATHRU_BEB-Pad31)") (class "Default")
      (node (ref "ATHRU_BEB") (pin "31") (pinfunction "31_31") (pintype "bidirectional"))
      (node (ref "ATHRU_TEB") (pin "31") (pinfunction "31_31") (pintype "bidirectional"))
    )
    (net (code "201") (name "Net-(ATHRU_BEB-Pad32)") (class "Default")
      (node (ref "ATHRU_BEB") (pin "32") (pinfunction "32_32") (pintype "bidirectional"))
      (node (ref "ATHRU_TEB") (pin "32") (pinfunction "32_32") (pintype "bidirectional"))
    )
    (net (code "202") (name "Net-(ATHRU_BEB-Pad33)") (class "Default")
      (node (ref "ATHRU_BEB") (pin "33") (pinfunction "33_33") (pintype "bidirectional"))
      (node (ref "ATHRU_TEB") (pin "33") (pinfunction "33_33") (pintype "bidirectional"))
    )
    (net (code "203") (name "Net-(ATHRU_BEB-Pad37)") (class "Default")
      (node (ref "ATHRU_BEB") (pin "37") (pinfunction "37_37") (pintype "bidirectional"))
      (node (ref "ATHRU_TEB") (pin "37") (pinfunction "37_37") (pintype "bidirectional"))
    )
    (net (code "204") (name "Net-(ATHRU_BEB-Pad38)") (class "Default")
      (node (ref "ATHRU_BEB") (pin "38") (pinfunction "38_38") (pintype "bidirectional"))
      (node (ref "ATHRU_TEB") (pin "38") (pinfunction "38_38") (pintype "bidirectional"))
    )
    (net (code "205") (name "Net-(ATHRU_BEB-Pad39)") (class "Default")
      (node (ref "ATHRU_BEB") (pin "39") (pinfunction "39_39") (pintype "bidirectional"))
      (node (ref "ATHRU_TEB") (pin "39") (pinfunction "39_39") (pintype "bidirectional"))
    )
    (net (code "206") (name "Net-(ATHRU_BEB-Pad40)") (class "Default")
      (node (ref "ATHRU_BEB") (pin "40") (pinfunction "40_40") (pintype "bidirectional"))
      (node (ref "ATHRU_TEB") (pin "40") (pinfunction "40_40") (pintype "bidirectional"))
    )
    (net (code "207") (name "Net-(ATHRU_BEB-Pad41)") (class "Default")
      (node (ref "ATHRU_BEB") (pin "41") (pinfunction "41_41") (pintype "bidirectional"))
      (node (ref "ATHRU_TEB") (pin "41") (pinfunction "41_41") (pintype "bidirectional"))
    )
    (net (code "208") (name "Net-(ATHRU_BEB-Pad42)") (class "Default")
      (node (ref "ATHRU_BEB") (pin "42") (pinfunction "42_42") (pintype "bidirectional"))
      (node (ref "ATHRU_TEB") (pin "42") (pinfunction "42_42") (pintype "bidirectional"))
    )
    (net (code "209") (name "Net-(ATHRU_BEB-Pad43)") (class "Default")
      (node (ref "ATHRU_BEB") (pin "43") (pinfunction "43_43") (pintype "bidirectional"))
      (node (ref "ATHRU_TEB") (pin "43") (pinfunction "43_43") (pintype "bidirectional"))
    )
    (net (code "210") (name "Net-(ATHRU_BEB-Pad44)") (class "Default")
      (node (ref "ATHRU_BEB") (pin "44") (pinfunction "44_44") (pintype "bidirectional"))
      (node (ref "ATHRU_TEB") (pin "44") (pinfunction "44_44") (pintype "bidirectional"))
    )
    (net (code "211") (name "Net-(ATHRU_BEB-Pad45)") (class "Default")
      (node (ref "ATHRU_BEB") (pin "45") (pinfunction "45_45") (pintype "bidirectional"))
      (node (ref "ATHRU_TEB") (pin "45") (pinfunction "45_45") (pintype "bidirectional"))
    )
    (net (code "212") (name "Net-(ATHRU_BEB-Pad46)") (class "Default")
      (node (ref "ATHRU_BEB") (pin "46") (pinfunction "46_46") (pintype "bidirectional"))
      (node (ref "ATHRU_TEB") (pin "46") (pinfunction "46_46") (pintype "bidirectional"))
    )
    (net (code "213") (name "Net-(ATHRU_BEB-Pad47)") (class "Default")
      (node (ref "ATHRU_BEB") (pin "47") (pinfunction "47_47") (pintype "bidirectional"))
      (node (ref "ATHRU_TEB") (pin "47") (pinfunction "47_47") (pintype "bidirectional"))
    )
    (net (code "214") (name "Net-(ATHRU_BEB-Pad48)") (class "Default")
      (node (ref "ATHRU_BEB") (pin "48") (pinfunction "48_48") (pintype "bidirectional"))
      (node (ref "ATHRU_TEB") (pin "48") (pinfunction "48_48") (pintype "bidirectional"))
    )
    (net (code "215") (name "Net-(ATHRU_BEB-Pad49)") (class "Default")
      (node (ref "ATHRU_BEB") (pin "49") (pinfunction "49_49") (pintype "bidirectional"))
      (node (ref "ATHRU_TEB") (pin "49") (pinfunction "49_49") (pintype "bidirectional"))
    )
    (net (code "216") (name "Net-(ATHRU_BEB-Pad50)") (class "Default")
      (node (ref "ATHRU_BEB") (pin "50") (pinfunction "50_50") (pintype "bidirectional"))
      (node (ref "ATHRU_TEB") (pin "50") (pinfunction "50_50") (pintype "bidirectional"))
    )
    (net (code "217") (name "Net-(ATHRU_BEB-Pad51)") (class "Default")
      (node (ref "ATHRU_BEB") (pin "51") (pinfunction "51_51") (pintype "bidirectional"))
      (node (ref "ATHRU_TEB") (pin "51") (pinfunction "51_51") (pintype "bidirectional"))
    )
    (net (code "218") (name "Net-(ATHRU_BEB-Pad52)") (class "Default")
      (node (ref "ATHRU_BEB") (pin "52") (pinfunction "52_52") (pintype "bidirectional"))
      (node (ref "ATHRU_TEB") (pin "52") (pinfunction "52_52") (pintype "bidirectional"))
    )
    (net (code "219") (name "Net-(ATHRU_BEB-Pad53)") (class "Default")
      (node (ref "ATHRU_BEB") (pin "53") (pinfunction "53_53") (pintype "bidirectional"))
      (node (ref "ATHRU_TEB") (pin "53") (pinfunction "53_53") (pintype "bidirectional"))
    )
    (net (code "220") (name "Net-(ATHRU_BEB-Pad54)") (class "Default")
      (node (ref "ATHRU_BEB") (pin "54") (pinfunction "54_54") (pintype "bidirectional"))
      (node (ref "ATHRU_TEB") (pin "54") (pinfunction "54_54") (pintype "bidirectional"))
    )
    (net (code "221") (name "Net-(ATHRU_BEB-Pad55)") (class "Default")
      (node (ref "ATHRU_BEB") (pin "55") (pinfunction "55_55") (pintype "bidirectional"))
      (node (ref "ATHRU_TEB") (pin "55") (pinfunction "55_55") (pintype "bidirectional"))
    )
    (net (code "222") (name "Net-(ATHRU_BEB-Pad56)") (class "Default")
      (node (ref "ATHRU_BEB") (pin "56") (pinfunction "56_56") (pintype "bidirectional"))
      (node (ref "ATHRU_TEB") (pin "56") (pinfunction "56_56") (pintype "bidirectional"))
    )
    (net (code "223") (name "Net-(ATHRU_BEB-Pad57)") (class "Default")
      (node (ref "ATHRU_BEB") (pin "57") (pinfunction "57_57") (pintype "bidirectional"))
      (node (ref "ATHRU_TEB") (pin "57") (pinfunction "57_57") (pintype "bidirectional"))
    )
    (net (code "224") (name "Net-(ATHRU_BEB-Pad58)") (class "Default")
      (node (ref "ATHRU_BEB") (pin "58") (pinfunction "58_58") (pintype "bidirectional"))
      (node (ref "ATHRU_TEB") (pin "58") (pinfunction "58_58") (pintype "bidirectional"))
    )
    (net (code "225") (name "Net-(ATHRU_BEB-Pad59)") (class "Default")
      (node (ref "ATHRU_BEB") (pin "59") (pinfunction "59_59") (pintype "bidirectional"))
      (node (ref "ATHRU_TEB") (pin "59") (pinfunction "59_59") (pintype "bidirectional"))
    )
    (net (code "226") (name "Net-(ATHRU_BEB-Pad60)") (class "Default")
      (node (ref "ATHRU_BEB") (pin "60") (pinfunction "60_60") (pintype "bidirectional"))
      (node (ref "ATHRU_TEB") (pin "60") (pinfunction "60_60") (pintype "bidirectional"))
    )
    (net (code "227") (name "Net-(ATHRU_BEB-Pad61)") (class "Default")
      (node (ref "ATHRU_BEB") (pin "61") (pinfunction "61_61") (pintype "bidirectional"))
      (node (ref "ATHRU_TEB") (pin "61") (pinfunction "61_61") (pintype "bidirectional"))
    )
    (net (code "228") (name "Net-(ATHRU_BEB-Pad62)") (class "Default")
      (node (ref "ATHRU_BEB") (pin "62") (pinfunction "62_62") (pintype "bidirectional"))
      (node (ref "ATHRU_TEB") (pin "62") (pinfunction "62_62") (pintype "bidirectional"))
    )
    (net (code "229") (name "Net-(ATHRU_BEB-Pad63)") (class "Default")
      (node (ref "ATHRU_BEB") (pin "63") (pinfunction "63_63") (pintype "bidirectional"))
      (node (ref "ATHRU_TEB") (pin "63") (pinfunction "63_63") (pintype "bidirectional"))
    )
    (net (code "230") (name "Net-(ATHRU_BEB-Pad64)") (class "Default")
      (node (ref "ATHRU_BEB") (pin "64") (pinfunction "64_64") (pintype "bidirectional"))
      (node (ref "ATHRU_TEB") (pin "64") (pinfunction "64_64") (pintype "bidirectional"))
    )
    (net (code "231") (name "Net-(ATHRU_BEB-Pad65)") (class "Default")
      (node (ref "ATHRU_BEB") (pin "65") (pinfunction "65_65") (pintype "bidirectional"))
      (node (ref "ATHRU_TEB") (pin "65") (pinfunction "65_65") (pintype "bidirectional"))
    )
    (net (code "232") (name "Net-(ATHRU_BEB-Pad66)") (class "Default")
      (node (ref "ATHRU_BEB") (pin "66") (pinfunction "66_66") (pintype "bidirectional"))
      (node (ref "ATHRU_TEB") (pin "66") (pinfunction "66_66") (pintype "bidirectional"))
    )
    (net (code "233") (name "Net-(ATHRU_BEB-Pad67)") (class "Default")
      (node (ref "ATHRU_BEB") (pin "67") (pinfunction "67_67") (pintype "bidirectional"))
      (node (ref "ATHRU_TEB") (pin "67") (pinfunction "67_67") (pintype "bidirectional"))
    )
    (net (code "234") (name "Net-(ATHRU_BEB-Pad68)") (class "Default")
      (node (ref "ATHRU_BEB") (pin "68") (pinfunction "68_68") (pintype "bidirectional"))
      (node (ref "ATHRU_TEB") (pin "68") (pinfunction "68_68") (pintype "bidirectional"))
    )
    (net (code "235") (name "Net-(ATHRU_BWB-Pad2)") (class "Default")
      (node (ref "ATHRU_BWB") (pin "2") (pinfunction "2_2") (pintype "bidirectional"))
      (node (ref "ATHRU_TWB") (pin "2") (pinfunction "2_2") (pintype "bidirectional"))
    )
    (net (code "236") (name "Net-(ATHRU_BWB-Pad3)") (class "Default")
      (node (ref "ATHRU_BWB") (pin "3") (pinfunction "3_3") (pintype "bidirectional"))
      (node (ref "ATHRU_TWB") (pin "3") (pinfunction "3_3") (pintype "bidirectional"))
    )
    (net (code "237") (name "Net-(ATHRU_BWB-Pad4)") (class "Default")
      (node (ref "ATHRU_BWB") (pin "4") (pinfunction "4_4") (pintype "bidirectional"))
      (node (ref "ATHRU_TWB") (pin "4") (pinfunction "4_4") (pintype "bidirectional"))
    )
    (net (code "238") (name "Net-(ATHRU_BWB-Pad5)") (class "Default")
      (node (ref "ATHRU_BWB") (pin "5") (pinfunction "5_5") (pintype "bidirectional"))
      (node (ref "ATHRU_TWB") (pin "5") (pinfunction "5_5") (pintype "bidirectional"))
    )
    (net (code "239") (name "Net-(ATHRU_BWB-Pad6)") (class "Default")
      (node (ref "ATHRU_BWB") (pin "6") (pinfunction "6_6") (pintype "bidirectional"))
      (node (ref "ATHRU_TWB") (pin "6") (pinfunction "6_6") (pintype "bidirectional"))
    )
    (net (code "240") (name "Net-(ATHRU_BWB-Pad7)") (class "Default")
      (node (ref "ATHRU_BWB") (pin "7") (pinfunction "7_7") (pintype "bidirectional"))
      (node (ref "ATHRU_TWB") (pin "7") (pinfunction "7_7") (pintype "bidirectional"))
    )
    (net (code "241") (name "Net-(ATHRU_BWB-Pad8)") (class "Default")
      (node (ref "ATHRU_BWB") (pin "8") (pinfunction "8_8") (pintype "bidirectional"))
      (node (ref "ATHRU_TWB") (pin "8") (pinfunction "8_8") (pintype "bidirectional"))
    )
    (net (code "242") (name "Net-(ATHRU_BWB-Pad9)") (class "Default")
      (node (ref "ATHRU_BWB") (pin "9") (pinfunction "9_9") (pintype "bidirectional"))
      (node (ref "ATHRU_TWB") (pin "9") (pinfunction "9_9") (pintype "bidirectional"))
    )
    (net (code "243") (name "Net-(ATHRU_BWB-Pad10)") (class "Default")
      (node (ref "ATHRU_BWB") (pin "10") (pinfunction "10_10") (pintype "bidirectional"))
      (node (ref "ATHRU_TWB") (pin "10") (pinfunction "10_10") (pintype "bidirectional"))
    )
    (net (code "244") (name "Net-(ATHRU_BWB-Pad11)") (class "Default")
      (node (ref "ATHRU_BWB") (pin "11") (pinfunction "11_11") (pintype "bidirectional"))
      (node (ref "ATHRU_TWB") (pin "11") (pinfunction "11_11") (pintype "bidirectional"))
    )
    (net (code "245") (name "Net-(ATHRU_BWB-Pad12)") (class "Default")
      (node (ref "ATHRU_BWB") (pin "12") (pinfunction "12_12") (pintype "bidirectional"))
      (node (ref "ATHRU_TWB") (pin "12") (pinfunction "12_12") (pintype "bidirectional"))
    )
    (net (code "246") (name "Net-(ATHRU_BWB-Pad13)") (class "Default")
      (node (ref "ATHRU_BWB") (pin "13") (pinfunction "13_13") (pintype "bidirectional"))
      (node (ref "ATHRU_TWB") (pin "13") (pinfunction "13_13") (pintype "bidirectional"))
    )
    (net (code "247") (name "Net-(ATHRU_BWB-Pad14)") (class "Default")
      (node (ref "ATHRU_BWB") (pin "14") (pinfunction "14_14") (pintype "bidirectional"))
      (node (ref "ATHRU_TWB") (pin "14") (pinfunction "14_14") (pintype "bidirectional"))
    )
    (net (code "248") (name "Net-(ATHRU_BWB-Pad15)") (class "Default")
      (node (ref "ATHRU_BWB") (pin "15") (pinfunction "15_15") (pintype "bidirectional"))
      (node (ref "ATHRU_TWB") (pin "15") (pinfunction "15_15") (pintype "bidirectional"))
    )
    (net (code "249") (name "Net-(ATHRU_BWB-Pad16)") (class "Default")
      (node (ref "ATHRU_BWB") (pin "16") (pinfunction "16_16") (pintype "bidirectional"))
      (node (ref "ATHRU_TWB") (pin "16") (pinfunction "16_16") (pintype "bidirectional"))
    )
    (net (code "250") (name "Net-(ATHRU_BWB-Pad17)") (class "Default")
      (node (ref "ATHRU_BWB") (pin "17") (pinfunction "17_17") (pintype "bidirectional"))
      (node (ref "ATHRU_TWB") (pin "17") (pinfunction "17_17") (pintype "bidirectional"))
    )
    (net (code "251") (name "Net-(ATHRU_BWB-Pad18)") (class "Default")
      (node (ref "ATHRU_BWB") (pin "18") (pinfunction "18_18") (pintype "bidirectional"))
      (node (ref "ATHRU_TWB") (pin "18") (pinfunction "18_18") (pintype "bidirectional"))
    )
    (net (code "252") (name "Net-(ATHRU_BWB-Pad19)") (class "Default")
      (node (ref "ATHRU_BWB") (pin "19") (pinfunction "19_19") (pintype "bidirectional"))
      (node (ref "ATHRU_TWB") (pin "19") (pinfunction "19_19") (pintype "bidirectional"))
    )
    (net (code "253") (name "Net-(ATHRU_BWB-Pad20)") (class "Default")
      (node (ref "ATHRU_BWB") (pin "20") (pinfunction "20_20") (pintype "bidirectional"))
      (node (ref "ATHRU_TWB") (pin "20") (pinfunction "20_20") (pintype "bidirectional"))
    )
    (net (code "254") (name "Net-(ATHRU_BWB-Pad21)") (class "Default")
      (node (ref "ATHRU_BWB") (pin "21") (pinfunction "21_21") (pintype "bidirectional"))
      (node (ref "ATHRU_TWB") (pin "21") (pinfunction "21_21") (pintype "bidirectional"))
    )
    (net (code "255") (name "Net-(ATHRU_BWB-Pad22)") (class "Default")
      (node (ref "ATHRU_BWB") (pin "22") (pinfunction "22_22") (pintype "bidirectional"))
      (node (ref "ATHRU_TWB") (pin "22") (pinfunction "22_22") (pintype "bidirectional"))
    )
    (net (code "256") (name "Net-(ATHRU_BWB-Pad23)") (class "Default")
      (node (ref "ATHRU_BWB") (pin "23") (pinfunction "23_23") (pintype "bidirectional"))
      (node (ref "ATHRU_TWB") (pin "23") (pinfunction "23_23") (pintype "bidirectional"))
    )
    (net (code "257") (name "Net-(ATHRU_BWB-Pad24)") (class "Default")
      (node (ref "ATHRU_BWB") (pin "24") (pinfunction "24_24") (pintype "bidirectional"))
      (node (ref "ATHRU_TWB") (pin "24") (pinfunction "24_24") (pintype "bidirectional"))
    )
    (net (code "258") (name "Net-(ATHRU_BWB-Pad25)") (class "Default")
      (node (ref "ATHRU_BWB") (pin "25") (pinfunction "25_25") (pintype "bidirectional"))
      (node (ref "ATHRU_TWB") (pin "25") (pinfunction "25_25") (pintype "bidirectional"))
    )
    (net (code "259") (name "Net-(ATHRU_BWB-Pad26)") (class "Default")
      (node (ref "ATHRU_BWB") (pin "26") (pinfunction "26_26") (pintype "bidirectional"))
      (node (ref "ATHRU_TWB") (pin "26") (pinfunction "26_26") (pintype "bidirectional"))
    )
    (net (code "260") (name "Net-(ATHRU_BWB-Pad27)") (class "Default")
      (node (ref "ATHRU_BWB") (pin "27") (pinfunction "27_27") (pintype "bidirectional"))
      (node (ref "ATHRU_TWB") (pin "27") (pinfunction "27_27") (pintype "bidirectional"))
    )
    (net (code "261") (name "Net-(ATHRU_BWB-Pad28)") (class "Default")
      (node (ref "ATHRU_BWB") (pin "28") (pinfunction "28_28") (pintype "bidirectional"))
      (node (ref "ATHRU_TWB") (pin "28") (pinfunction "28_28") (pintype "bidirectional"))
    )
    (net (code "262") (name "Net-(ATHRU_BWB-Pad29)") (class "Default")
      (node (ref "ATHRU_BWB") (pin "29") (pinfunction "29_29") (pintype "bidirectional"))
      (node (ref "ATHRU_TWB") (pin "29") (pinfunction "29_29") (pintype "bidirectional"))
    )
    (net (code "263") (name "Net-(ATHRU_BWB-Pad30)") (class "Default")
      (node (ref "ATHRU_BWB") (pin "30") (pinfunction "30_30") (pintype "bidirectional"))
      (node (ref "ATHRU_TWB") (pin "30") (pinfunction "30_30") (pintype "bidirectional"))
    )
    (net (code "264") (name "Net-(ATHRU_BWB-Pad31)") (class "Default")
      (node (ref "ATHRU_BWB") (pin "31") (pinfunction "31_31") (pintype "bidirectional"))
      (node (ref "ATHRU_TWB") (pin "31") (pinfunction "31_31") (pintype "bidirectional"))
    )
    (net (code "265") (name "Net-(ATHRU_BWB-Pad32)") (class "Default")
      (node (ref "ATHRU_BWB") (pin "32") (pinfunction "32_32") (pintype "bidirectional"))
      (node (ref "ATHRU_TWB") (pin "32") (pinfunction "32_32") (pintype "bidirectional"))
    )
    (net (code "266") (name "Net-(ATHRU_BWB-Pad33)") (class "Default")
      (node (ref "ATHRU_BWB") (pin "33") (pinfunction "33_33") (pintype "bidirectional"))
      (node (ref "ATHRU_TWB") (pin "33") (pinfunction "33_33") (pintype "bidirectional"))
    )
    (net (code "267") (name "Net-(ATHRU_BWB-Pad37)") (class "Default")
      (node (ref "ATHRU_BWB") (pin "37") (pinfunction "37_37") (pintype "bidirectional"))
      (node (ref "ATHRU_TWB") (pin "37") (pinfunction "37_37") (pintype "bidirectional"))
    )
    (net (code "268") (name "Net-(ATHRU_BWB-Pad38)") (class "Default")
      (node (ref "ATHRU_BWB") (pin "38") (pinfunction "38_38") (pintype "bidirectional"))
      (node (ref "ATHRU_TWB") (pin "38") (pinfunction "38_38") (pintype "bidirectional"))
    )
    (net (code "269") (name "Net-(ATHRU_BWB-Pad39)") (class "Default")
      (node (ref "ATHRU_BWB") (pin "39") (pinfunction "39_39") (pintype "bidirectional"))
      (node (ref "ATHRU_TWB") (pin "39") (pinfunction "39_39") (pintype "bidirectional"))
    )
    (net (code "270") (name "Net-(ATHRU_BWB-Pad40)") (class "Default")
      (node (ref "ATHRU_BWB") (pin "40") (pinfunction "40_40") (pintype "bidirectional"))
      (node (ref "ATHRU_TWB") (pin "40") (pinfunction "40_40") (pintype "bidirectional"))
    )
    (net (code "271") (name "Net-(ATHRU_BWB-Pad41)") (class "Default")
      (node (ref "ATHRU_BWB") (pin "41") (pinfunction "41_41") (pintype "bidirectional"))
      (node (ref "ATHRU_TWB") (pin "41") (pinfunction "41_41") (pintype "bidirectional"))
    )
    (net (code "272") (name "Net-(ATHRU_BWB-Pad42)") (class "Default")
      (node (ref "ATHRU_BWB") (pin "42") (pinfunction "42_42") (pintype "bidirectional"))
      (node (ref "ATHRU_TWB") (pin "42") (pinfunction "42_42") (pintype "bidirectional"))
    )
    (net (code "273") (name "Net-(ATHRU_BWB-Pad43)") (class "Default")
      (node (ref "ATHRU_BWB") (pin "43") (pinfunction "43_43") (pintype "bidirectional"))
      (node (ref "ATHRU_TWB") (pin "43") (pinfunction "43_43") (pintype "bidirectional"))
    )
    (net (code "274") (name "Net-(ATHRU_BWB-Pad44)") (class "Default")
      (node (ref "ATHRU_BWB") (pin "44") (pinfunction "44_44") (pintype "bidirectional"))
      (node (ref "ATHRU_TWB") (pin "44") (pinfunction "44_44") (pintype "bidirectional"))
    )
    (net (code "275") (name "Net-(ATHRU_BWB-Pad45)") (class "Default")
      (node (ref "ATHRU_BWB") (pin "45") (pinfunction "45_45") (pintype "bidirectional"))
      (node (ref "ATHRU_TWB") (pin "45") (pinfunction "45_45") (pintype "bidirectional"))
    )
    (net (code "276") (name "Net-(ATHRU_BWB-Pad46)") (class "Default")
      (node (ref "ATHRU_BWB") (pin "46") (pinfunction "46_46") (pintype "bidirectional"))
      (node (ref "ATHRU_TWB") (pin "46") (pinfunction "46_46") (pintype "bidirectional"))
    )
    (net (code "277") (name "Net-(ATHRU_BWB-Pad47)") (class "Default")
      (node (ref "ATHRU_BWB") (pin "47") (pinfunction "47_47") (pintype "bidirectional"))
      (node (ref "ATHRU_TWB") (pin "47") (pinfunction "47_47") (pintype "bidirectional"))
    )
    (net (code "278") (name "Net-(ATHRU_BWB-Pad48)") (class "Default")
      (node (ref "ATHRU_BWB") (pin "48") (pinfunction "48_48") (pintype "bidirectional"))
      (node (ref "ATHRU_TWB") (pin "48") (pinfunction "48_48") (pintype "bidirectional"))
    )
    (net (code "279") (name "Net-(ATHRU_BWB-Pad49)") (class "Default")
      (node (ref "ATHRU_BWB") (pin "49") (pinfunction "49_49") (pintype "bidirectional"))
      (node (ref "ATHRU_TWB") (pin "49") (pinfunction "49_49") (pintype "bidirectional"))
    )
    (net (code "280") (name "Net-(ATHRU_BWB-Pad50)") (class "Default")
      (node (ref "ATHRU_BWB") (pin "50") (pinfunction "50_50") (pintype "bidirectional"))
      (node (ref "ATHRU_TWB") (pin "50") (pinfunction "50_50") (pintype "bidirectional"))
    )
    (net (code "281") (name "Net-(ATHRU_BWB-Pad51)") (class "Default")
      (node (ref "ATHRU_BWB") (pin "51") (pinfunction "51_51") (pintype "bidirectional"))
      (node (ref "ATHRU_TWB") (pin "51") (pinfunction "51_51") (pintype "bidirectional"))
    )
    (net (code "282") (name "Net-(ATHRU_BWB-Pad52)") (class "Default")
      (node (ref "ATHRU_BWB") (pin "52") (pinfunction "52_52") (pintype "bidirectional"))
      (node (ref "ATHRU_TWB") (pin "52") (pinfunction "52_52") (pintype "bidirectional"))
    )
    (net (code "283") (name "Net-(ATHRU_BWB-Pad53)") (class "Default")
      (node (ref "ATHRU_BWB") (pin "53") (pinfunction "53_53") (pintype "bidirectional"))
      (node (ref "ATHRU_TWB") (pin "53") (pinfunction "53_53") (pintype "bidirectional"))
    )
    (net (code "284") (name "Net-(ATHRU_BWB-Pad54)") (class "Default")
      (node (ref "ATHRU_BWB") (pin "54") (pinfunction "54_54") (pintype "bidirectional"))
      (node (ref "ATHRU_TWB") (pin "54") (pinfunction "54_54") (pintype "bidirectional"))
    )
    (net (code "285") (name "Net-(ATHRU_BWB-Pad55)") (class "Default")
      (node (ref "ATHRU_BWB") (pin "55") (pinfunction "55_55") (pintype "bidirectional"))
      (node (ref "ATHRU_TWB") (pin "55") (pinfunction "55_55") (pintype "bidirectional"))
    )
    (net (code "286") (name "Net-(ATHRU_BWB-Pad56)") (class "Default")
      (node (ref "ATHRU_BWB") (pin "56") (pinfunction "56_56") (pintype "bidirectional"))
      (node (ref "ATHRU_TWB") (pin "56") (pinfunction "56_56") (pintype "bidirectional"))
    )
    (net (code "287") (name "Net-(ATHRU_BWB-Pad57)") (class "Default")
      (node (ref "ATHRU_BWB") (pin "57") (pinfunction "57_57") (pintype "bidirectional"))
      (node (ref "ATHRU_TWB") (pin "57") (pinfunction "57_57") (pintype "bidirectional"))
    )
    (net (code "288") (name "Net-(ATHRU_BWB-Pad58)") (class "Default")
      (node (ref "ATHRU_BWB") (pin "58") (pinfunction "58_58") (pintype "bidirectional"))
      (node (ref "ATHRU_TWB") (pin "58") (pinfunction "58_58") (pintype "bidirectional"))
    )
    (net (code "289") (name "Net-(ATHRU_BWB-Pad59)") (class "Default")
      (node (ref "ATHRU_BWB") (pin "59") (pinfunction "59_59") (pintype "bidirectional"))
      (node (ref "ATHRU_TWB") (pin "59") (pinfunction "59_59") (pintype "bidirectional"))
    )
    (net (code "290") (name "Net-(ATHRU_BWB-Pad60)") (class "Default")
      (node (ref "ATHRU_BWB") (pin "60") (pinfunction "60_60") (pintype "bidirectional"))
      (node (ref "ATHRU_TWB") (pin "60") (pinfunction "60_60") (pintype "bidirectional"))
    )
    (net (code "291") (name "Net-(ATHRU_BWB-Pad61)") (class "Default")
      (node (ref "ATHRU_BWB") (pin "61") (pinfunction "61_61") (pintype "bidirectional"))
      (node (ref "ATHRU_TWB") (pin "61") (pinfunction "61_61") (pintype "bidirectional"))
    )
    (net (code "292") (name "Net-(ATHRU_BWB-Pad62)") (class "Default")
      (node (ref "ATHRU_BWB") (pin "62") (pinfunction "62_62") (pintype "bidirectional"))
      (node (ref "ATHRU_TWB") (pin "62") (pinfunction "62_62") (pintype "bidirectional"))
    )
    (net (code "293") (name "Net-(ATHRU_BWB-Pad63)") (class "Default")
      (node (ref "ATHRU_BWB") (pin "63") (pinfunction "63_63") (pintype "bidirectional"))
      (node (ref "ATHRU_TWB") (pin "63") (pinfunction "63_63") (pintype "bidirectional"))
    )
    (net (code "294") (name "Net-(ATHRU_BWB-Pad64)") (class "Default")
      (node (ref "ATHRU_BWB") (pin "64") (pinfunction "64_64") (pintype "bidirectional"))
      (node (ref "ATHRU_TWB") (pin "64") (pinfunction "64_64") (pintype "bidirectional"))
    )
    (net (code "295") (name "Net-(ATHRU_BWB-Pad65)") (class "Default")
      (node (ref "ATHRU_BWB") (pin "65") (pinfunction "65_65") (pintype "bidirectional"))
      (node (ref "ATHRU_TWB") (pin "65") (pinfunction "65_65") (pintype "bidirectional"))
    )
    (net (code "296") (name "Net-(ATHRU_BWB-Pad66)") (class "Default")
      (node (ref "ATHRU_BWB") (pin "66") (pinfunction "66_66") (pintype "bidirectional"))
      (node (ref "ATHRU_TWB") (pin "66") (pinfunction "66_66") (pintype "bidirectional"))
    )
    (net (code "297") (name "Net-(ATHRU_BWB-Pad67)") (class "Default")
      (node (ref "ATHRU_BWB") (pin "67") (pinfunction "67_67") (pintype "bidirectional"))
      (node (ref "ATHRU_TWB") (pin "67") (pinfunction "67_67") (pintype "bidirectional"))
    )
    (net (code "298") (name "Net-(ATHRU_BWB-Pad68)") (class "Default")
      (node (ref "ATHRU_BWB") (pin "68") (pinfunction "68_68") (pintype "bidirectional"))
      (node (ref "ATHRU_TWB") (pin "68") (pinfunction "68_68") (pintype "bidirectional"))
    )
    (net (code "299") (name "Net-(U2-1Y1)") (class "Default")
      (node (ref "PLT") (pin "B2") (pinfunction "B2_B2") (pintype "bidirectional"))
      (node (ref "U2") (pin "1") (pinfunction "2Y1_1") (pintype "bidirectional"))
      (node (ref "U2") (pin "13") (pinfunction "1Y1_13") (pintype "bidirectional"))
    )
    (net (code "300") (name "Net-(U2-3Y0)") (class "Default")
      (node (ref "R4") (pin "2") (pinfunction "2_2") (pintype "passive"))
      (node (ref "U2") (pin "5") (pinfunction "3Y0_5") (pintype "bidirectional"))
    )
    (net (code "301") (name "Net-(U2-S1)") (class "Default")
      (node (ref "PLT") (pin "T1") (pinfunction "T1_T1") (pintype "bidirectional"))
      (node (ref "R7") (pin "2") (pinfunction "2_2") (pintype "passive"))
      (node (ref "U2") (pin "11") (pinfunction "S1_11") (pintype "input"))
    )
    (net (code "302") (name "Net-(U2-S2)") (class "Default")
      (node (ref "PLT") (pin "T2") (pinfunction "T2_T2") (pintype "bidirectional"))
      (node (ref "R6") (pin "2") (pinfunction "2_2") (pintype "passive"))
      (node (ref "U2") (pin "10") (pinfunction "S2_10") (pintype "input"))
    )
    (net (code "303") (name "Net-(U2-S3)") (class "Default")
      (node (ref "PLT") (pin "T3") (pinfunction "T3_T3") (pintype "bidirectional"))
      (node (ref "R5") (pin "2") (pinfunction "2_2") (pintype "passive"))
      (node (ref "U2") (pin "9") (pinfunction "S3_9") (pintype "input"))
    )
    (net (code "304") (name "VCC") (class "Default")
      (node (ref "AMP_A") (pin "B17") (pinfunction "VDD2_B17") (pintype "power_in"))
      (node (ref "AMP_A") (pin "B18") (pinfunction "VDD3_B18") (pintype "power_in"))
      (node (ref "AMP_A") (pin "B2") (pinfunction "VESD_B2") (pintype "power_in"))
      (node (ref "AMP_A") (pin "B21") (pinfunction "LVDS_EN_B21") (pintype "input"))
      (node (ref "AMP_A") (pin "B4") (pinfunction "VDD1_B4") (pintype "power_in"))
      (node (ref "AMP_A") (pin "B5") (pinfunction "AUXIN1_B5") (pintype "input"))
      (node (ref "AMP_A") (pin "B6") (pinfunction "AUXIN2_B6") (pintype "input"))
      (node (ref "AMP_A") (pin "B7") (pinfunction "AUXIN3_B7") (pintype "input"))
      (node (ref "AMP_B") (pin "B17") (pinfunction "VDD2_B17") (pintype "power_in"))
      (node (ref "AMP_B") (pin "B18") (pinfunction "VDD3_B18") (pintype "power_in"))
      (node (ref "AMP_B") (pin "B2") (pinfunction "VESD_B2") (pintype "power_in"))
      (node (ref "AMP_B") (pin "B21") (pinfunction "LVDS_EN_B21") (pintype "input"))
      (node (ref "AMP_B") (pin "B4") (pinfunction "VDD1_B4") (pintype "power_in"))
      (node (ref "C2") (pin "1") (pinfunction "1_1") (pintype "passive"))
      (node (ref "C3") (pin "1") (pinfunction "1_1") (pintype "passive"))
      (node (ref "C8") (pin "1") (pinfunction "1_1") (pintype "passive"))
      (node (ref "DIO_TEA") (pin "10") (pinfunction "10_10") (pintype "bidirectional"))
      (node (ref "DIO_TEA") (pin "8") (pinfunction "8_8") (pintype "bidirectional"))
      (node (ref "DIO_TEA") (pin "9") (pinfunction "9_9") (pintype "bidirectional"))
      (node (ref "U1") (pin "VS1") (pinfunction "VS1_VS1") (pintype "bidirectional"))
      (node (ref "U1") (pin "VS2") (pinfunction "VS2_VS2") (pintype "bidirectional"))
      (node (ref "U2") (pin "16") (pinfunction "VCC_16") (pintype "power_in"))
      (node (ref "VCC1") (pin "1") (pinfunction "1_1") (pintype "passive"))
      (node (ref "VCC2") (pin "1") (pinfunction "1_1") (pintype "passive"))
    )
    (net (code "305") (name "unconnected-(AMP_A-AUXOUT-PadB20)") (class "Default")
      (node (ref "AMP_A") (pin "B20") (pinfunction "AUXOUT_B20") (pintype "tri_state"))
    )
    (net (code "306") (name "unconnected-(AMP_A-REF_ELEC1-PadA)") (class "Default")
      (node (ref "AMP_A") (pin "A") (pinfunction "REF_ELEC1_A") (pintype "input"))
    )
    (net (code "307") (name "unconnected-(AMP_A-REF_ELEC2-PadB)") (class "Default")
      (node (ref "AMP_A") (pin "B") (pinfunction "REF_ELEC2_B") (pintype "input"))
    )
    (net (code "308") (name "unconnected-(AMP_B-REF_ELEC1-PadA)") (class "Default")
      (node (ref "AMP_B") (pin "A") (pinfunction "REF_ELEC1_A") (pintype "input"))
    )
    (net (code "309") (name "unconnected-(AMP_B-REF_ELEC2-PadB)") (class "Default")
      (node (ref "AMP_B") (pin "B") (pinfunction "REF_ELEC2_B") (pintype "input"))
    )
    (net (code "310") (name "unconnected-(MECH_TNB-Pad1)") (class "Default")
      (node (ref "MECH_TNB") (pin "1") (pinfunction "1_1") (pintype "bidirectional"))
    )
    (net (code "311") (name "unconnected-(MECH_TNB-Pad2)") (class "Default")
      (node (ref "MECH_TNB") (pin "2") (pinfunction "2_2") (pintype "bidirectional"))
    )
    (net (code "312") (name "unconnected-(MECH_TNB-Pad3)") (class "Default")
      (node (ref "MECH_TNB") (pin "3") (pinfunction "3_3") (pintype "bidirectional"))
    )
    (net (code "313") (name "unconnected-(MECH_TNB-Pad4)") (class "Default")
      (node (ref "MECH_TNB") (pin "4") (pinfunction "4_4") (pintype "bidirectional"))
    )
    (net (code "314") (name "unconnected-(MECH_TNB-Pad5)") (class "Default")
      (node (ref "MECH_TNB") (pin "5") (pinfunction "5_5") (pintype "bidirectional"))
    )
    (net (code "315") (name "unconnected-(MECH_TNB-Pad6)") (class "Default")
      (node (ref "MECH_TNB") (pin "6") (pinfunction "6_6") (pintype "bidirectional"))
    )
    (net (code "316") (name "unconnected-(MECH_TNB-Pad7)") (class "Default")
      (node (ref "MECH_TNB") (pin "7") (pinfunction "7_7") (pintype "bidirectional"))
    )
    (net (code "317") (name "unconnected-(MECH_TNB-Pad8)") (class "Default")
      (node (ref "MECH_TNB") (pin "8") (pinfunction "8_8") (pintype "bidirectional"))
    )
    (net (code "318") (name "unconnected-(MECH_TNB-Pad9)") (class "Default")
      (node (ref "MECH_TNB") (pin "9") (pinfunction "9_9") (pintype "bidirectional"))
    )
    (net (code "319") (name "unconnected-(MECH_TNB-Pad10)") (class "Default")
      (node (ref "MECH_TNB") (pin "10") (pinfunction "10_10") (pintype "bidirectional"))
    )
    (net (code "320") (name "unconnected-(MECH_TNB-Pad11)") (class "Default")
      (node (ref "MECH_TNB") (pin "11") (pinfunction "11_11") (pintype "bidirectional"))
    )
    (net (code "321") (name "unconnected-(MECH_TNB-Pad12)") (class "Default")
      (node (ref "MECH_TNB") (pin "12") (pinfunction "12_12") (pintype "bidirectional"))
    )
    (net (code "322") (name "unconnected-(MECH_TNB-Pad13)") (class "Default")
      (node (ref "MECH_TNB") (pin "13") (pinfunction "13_13") (pintype "bidirectional"))
    )
    (net (code "323") (name "unconnected-(MECH_TNB-Pad14)") (class "Default")
      (node (ref "MECH_TNB") (pin "14") (pinfunction "14_14") (pintype "bidirectional"))
    )
    (net (code "324") (name "unconnected-(MECH_TNB-Pad15)") (class "Default")
      (node (ref "MECH_TNB") (pin "15") (pinfunction "15_15") (pintype "bidirectional"))
    )
    (net (code "325") (name "unconnected-(MECH_TNB-Pad16)") (class "Default")
      (node (ref "MECH_TNB") (pin "16") (pinfunction "16_16") (pintype "bidirectional"))
    )
    (net (code "326") (name "unconnected-(MECH_TNB-Pad17)") (class "Default")
      (node (ref "MECH_TNB") (pin "17") (pinfunction "17_17") (pintype "bidirectional"))
    )
    (net (code "327") (name "unconnected-(MECH_TNB-Pad18)") (class "Default")
      (node (ref "MECH_TNB") (pin "18") (pinfunction "18_18") (pintype "bidirectional"))
    )
    (net (code "328") (name "unconnected-(MECH_TNB-Pad19)") (class "Default")
      (node (ref "MECH_TNB") (pin "19") (pinfunction "19_19") (pintype "bidirectional"))
    )
    (net (code "329") (name "unconnected-(MECH_TNB-Pad20)") (class "Default")
      (node (ref "MECH_TNB") (pin "20") (pinfunction "20_20") (pintype "bidirectional"))
    )
    (net (code "330") (name "unconnected-(MECH_TNB-Pad21)") (class "Default")
      (node (ref "MECH_TNB") (pin "21") (pinfunction "21_21") (pintype "bidirectional"))
    )
    (net (code "331") (name "unconnected-(MECH_TNB-Pad22)") (class "Default")
      (node (ref "MECH_TNB") (pin "22") (pinfunction "22_22") (pintype "bidirectional"))
    )
    (net (code "332") (name "unconnected-(MECH_TNB-Pad23)") (class "Default")
      (node (ref "MECH_TNB") (pin "23") (pinfunction "23_23") (pintype "bidirectional"))
    )
    (net (code "333") (name "unconnected-(MECH_TNB-Pad24)") (class "Default")
      (node (ref "MECH_TNB") (pin "24") (pinfunction "24_24") (pintype "bidirectional"))
    )
    (net (code "334") (name "unconnected-(MECH_TNB-Pad25)") (class "Default")
      (node (ref "MECH_TNB") (pin "25") (pinfunction "25_25") (pintype "bidirectional"))
    )
    (net (code "335") (name "unconnected-(MECH_TNB-Pad26)") (class "Default")
      (node (ref "MECH_TNB") (pin "26") (pinfunction "26_26") (pintype "bidirectional"))
    )
    (net (code "336") (name "unconnected-(MECH_TNB-Pad27)") (class "Default")
      (node (ref "MECH_TNB") (pin "27") (pinfunction "27_27") (pintype "bidirectional"))
    )
    (net (code "337") (name "unconnected-(MECH_TNB-Pad28)") (class "Default")
      (node (ref "MECH_TNB") (pin "28") (pinfunction "28_28") (pintype "bidirectional"))
    )
    (net (code "338") (name "unconnected-(MECH_TNB-Pad29)") (class "Default")
      (node (ref "MECH_TNB") (pin "29") (pinfunction "29_29") (pintype "bidirectional"))
    )
    (net (code "339") (name "unconnected-(MECH_TNB-Pad30)") (class "Default")
      (node (ref "MECH_TNB") (pin "30") (pinfunction "30_30") (pintype "bidirectional"))
    )
    (net (code "340") (name "unconnected-(MECH_TNB-Pad31)") (class "Default")
      (node (ref "MECH_TNB") (pin "31") (pinfunction "31_31") (pintype "bidirectional"))
    )
    (net (code "341") (name "unconnected-(MECH_TNB-Pad32)") (class "Default")
      (node (ref "MECH_TNB") (pin "32") (pinfunction "32_32") (pintype "bidirectional"))
    )
    (net (code "342") (name "unconnected-(MECH_TNB-Pad33)") (class "Default")
      (node (ref "MECH_TNB") (pin "33") (pinfunction "33_33") (pintype "bidirectional"))
    )
    (net (code "343") (name "unconnected-(MECH_TNB-Pad34)") (class "Default")
      (node (ref "MECH_TNB") (pin "34") (pinfunction "34_34") (pintype "bidirectional"))
    )
    (net (code "344") (name "unconnected-(MECH_TNB-Pad35)") (class "Default")
      (node (ref "MECH_TNB") (pin "35") (pinfunction "35_35") (pintype "bidirectional"))
    )
    (net (code "345") (name "unconnected-(MECH_TNB-Pad36)") (class "Default")
      (node (ref "MECH_TNB") (pin "36") (pinfunction "36_36") (pintype "bidirectional"))
    )
    (net (code "346") (name "unconnected-(MECH_TNB-Pad37)") (class "Default")
      (node (ref "MECH_TNB") (pin "37") (pinfunction "37_37") (pintype "bidirectional"))
    )
    (net (code "347") (name "unconnected-(MECH_TNB-Pad38)") (class "Default")
      (node (ref "MECH_TNB") (pin "38") (pinfunction "38_38") (pintype "bidirectional"))
    )
    (net (code "348") (name "unconnected-(MECH_TNB-Pad39)") (class "Default")
      (node (ref "MECH_TNB") (pin "39") (pinfunction "39_39") (pintype "bidirectional"))
    )
    (net (code "349") (name "unconnected-(MECH_TNB-Pad40)") (class "Default")
      (node (ref "MECH_TNB") (pin "40") (pinfunction "40_40") (pintype "bidirectional"))
    )
    (net (code "350") (name "unconnected-(MECH_TNB-Pad41)") (class "Default")
      (node (ref "MECH_TNB") (pin "41") (pinfunction "41_41") (pintype "bidirectional"))
    )
    (net (code "351") (name "unconnected-(MECH_TNB-Pad42)") (class "Default")
      (node (ref "MECH_TNB") (pin "42") (pinfunction "42_42") (pintype "bidirectional"))
    )
    (net (code "352") (name "unconnected-(MECH_TNB-Pad43)") (class "Default")
      (node (ref "MECH_TNB") (pin "43") (pinfunction "43_43") (pintype "bidirectional"))
    )
    (net (code "353") (name "unconnected-(MECH_TNB-Pad44)") (class "Default")
      (node (ref "MECH_TNB") (pin "44") (pinfunction "44_44") (pintype "bidirectional"))
    )
    (net (code "354") (name "unconnected-(MECH_TNB-Pad45)") (class "Default")
      (node (ref "MECH_TNB") (pin "45") (pinfunction "45_45") (pintype "bidirectional"))
    )
    (net (code "355") (name "unconnected-(MECH_TNB-Pad46)") (class "Default")
      (node (ref "MECH_TNB") (pin "46") (pinfunction "46_46") (pintype "bidirectional"))
    )
    (net (code "356") (name "unconnected-(MECH_TNB-Pad47)") (class "Default")
      (node (ref "MECH_TNB") (pin "47") (pinfunction "47_47") (pintype "bidirectional"))
    )
    (net (code "357") (name "unconnected-(MECH_TNB-Pad48)") (class "Default")
      (node (ref "MECH_TNB") (pin "48") (pinfunction "48_48") (pintype "bidirectional"))
    )
    (net (code "358") (name "unconnected-(MECH_TNB-Pad49)") (class "Default")
      (node (ref "MECH_TNB") (pin "49") (pinfunction "49_49") (pintype "bidirectional"))
    )
    (net (code "359") (name "unconnected-(MECH_TNB-Pad50)") (class "Default")
      (node (ref "MECH_TNB") (pin "50") (pinfunction "50_50") (pintype "bidirectional"))
    )
    (net (code "360") (name "unconnected-(MECH_TNB-Pad51)") (class "Default")
      (node (ref "MECH_TNB") (pin "51") (pinfunction "51_51") (pintype "bidirectional"))
    )
    (net (code "361") (name "unconnected-(MECH_TNB-Pad52)") (class "Default")
      (node (ref "MECH_TNB") (pin "52") (pinfunction "52_52") (pintype "bidirectional"))
    )
    (net (code "362") (name "unconnected-(MECH_TNB-Pad53)") (class "Default")
      (node (ref "MECH_TNB") (pin "53") (pinfunction "53_53") (pintype "bidirectional"))
    )
    (net (code "363") (name "unconnected-(MECH_TNB-Pad54)") (class "Default")
      (node (ref "MECH_TNB") (pin "54") (pinfunction "54_54") (pintype "bidirectional"))
    )
    (net (code "364") (name "unconnected-(MECH_TNB-Pad55)") (class "Default")
      (node (ref "MECH_TNB") (pin "55") (pinfunction "55_55") (pintype "bidirectional"))
    )
    (net (code "365") (name "unconnected-(MECH_TNB-Pad56)") (class "Default")
      (node (ref "MECH_TNB") (pin "56") (pinfunction "56_56") (pintype "bidirectional"))
    )
    (net (code "366") (name "unconnected-(MECH_TNB-Pad57)") (class "Default")
      (node (ref "MECH_TNB") (pin "57") (pinfunction "57_57") (pintype "bidirectional"))
    )
    (net (code "367") (name "unconnected-(MECH_TNB-Pad58)") (class "Default")
      (node (ref "MECH_TNB") (pin "58") (pinfunction "58_58") (pintype "bidirectional"))
    )
    (net (code "368") (name "unconnected-(MECH_TNB-Pad59)") (class "Default")
      (node (ref "MECH_TNB") (pin "59") (pinfunction "59_59") (pintype "bidirectional"))
    )
    (net (code "369") (name "unconnected-(MECH_TNB-Pad60)") (class "Default")
      (node (ref "MECH_TNB") (pin "60") (pinfunction "60_60") (pintype "bidirectional"))
    )
    (net (code "370") (name "unconnected-(MECH_TNB-Pad61)") (class "Default")
      (node (ref "MECH_TNB") (pin "61") (pinfunction "61_61") (pintype "bidirectional"))
    )
    (net (code "371") (name "unconnected-(MECH_TNB-Pad62)") (class "Default")
      (node (ref "MECH_TNB") (pin "62") (pinfunction "62_62") (pintype "bidirectional"))
    )
    (net (code "372") (name "unconnected-(MECH_TNB-Pad63)") (class "Default")
      (node (ref "MECH_TNB") (pin "63") (pinfunction "63_63") (pintype "bidirectional"))
    )
    (net (code "373") (name "unconnected-(MECH_TNB-Pad64)") (class "Default")
      (node (ref "MECH_TNB") (pin "64") (pinfunction "64_64") (pintype "bidirectional"))
    )
    (net (code "374") (name "unconnected-(MECH_TNB-Pad65)") (class "Default")
      (node (ref "MECH_TNB") (pin "65") (pinfunction "65_65") (pintype "bidirectional"))
    )
    (net (code "375") (name "unconnected-(MECH_TNB-Pad66)") (class "Default")
      (node (ref "MECH_TNB") (pin "66") (pinfunction "66_66") (pintype "bidirectional"))
    )
    (net (code "376") (name "unconnected-(MECH_TNB-Pad67)") (class "Default")
      (node (ref "MECH_TNB") (pin "67") (pinfunction "67_67") (pintype "bidirectional"))
    )
    (net (code "377") (name "unconnected-(MECH_TNB-Pad68)") (class "Default")
      (node (ref "MECH_TNB") (pin "68") (pinfunction "68_68") (pintype "bidirectional"))
    )
    (net (code "378") (name "unconnected-(MECH_TNB-Pad69)") (class "Default")
      (node (ref "MECH_TNB") (pin "69") (pinfunction "69_69") (pintype "bidirectional"))
    )
    (net (code "379") (name "unconnected-(MECH_TNB-Pad70)") (class "Default")
      (node (ref "MECH_TNB") (pin "70") (pinfunction "70_70") (pintype "bidirectional"))
    )
    (net (code "380") (name "unconnected-(MECH_TSB-Pad1)") (class "Default")
      (node (ref "MECH_TSB") (pin "1") (pinfunction "1_1") (pintype "bidirectional"))
    )
    (net (code "381") (name "unconnected-(MECH_TSB-Pad2)") (class "Default")
      (node (ref "MECH_TSB") (pin "2") (pinfunction "2_2") (pintype "bidirectional"))
    )
    (net (code "382") (name "unconnected-(MECH_TSB-Pad3)") (class "Default")
      (node (ref "MECH_TSB") (pin "3") (pinfunction "3_3") (pintype "bidirectional"))
    )
    (net (code "383") (name "unconnected-(MECH_TSB-Pad4)") (class "Default")
      (node (ref "MECH_TSB") (pin "4") (pinfunction "4_4") (pintype "bidirectional"))
    )
    (net (code "384") (name "unconnected-(MECH_TSB-Pad5)") (class "Default")
      (node (ref "MECH_TSB") (pin "5") (pinfunction "5_5") (pintype "bidirectional"))
    )
    (net (code "385") (name "unconnected-(MECH_TSB-Pad6)") (class "Default")
      (node (ref "MECH_TSB") (pin "6") (pinfunction "6_6") (pintype "bidirectional"))
    )
    (net (code "386") (name "unconnected-(MECH_TSB-Pad7)") (class "Default")
      (node (ref "MECH_TSB") (pin "7") (pinfunction "7_7") (pintype "bidirectional"))
    )
    (net (code "387") (name "unconnected-(MECH_TSB-Pad8)") (class "Default")
      (node (ref "MECH_TSB") (pin "8") (pinfunction "8_8") (pintype "bidirectional"))
    )
    (net (code "388") (name "unconnected-(MECH_TSB-Pad9)") (class "Default")
      (node (ref "MECH_TSB") (pin "9") (pinfunction "9_9") (pintype "bidirectional"))
    )
    (net (code "389") (name "unconnected-(MECH_TSB-Pad10)") (class "Default")
      (node (ref "MECH_TSB") (pin "10") (pinfunction "10_10") (pintype "bidirectional"))
    )
    (net (code "390") (name "unconnected-(MECH_TSB-Pad11)") (class "Default")
      (node (ref "MECH_TSB") (pin "11") (pinfunction "11_11") (pintype "bidirectional"))
    )
    (net (code "391") (name "unconnected-(MECH_TSB-Pad12)") (class "Default")
      (node (ref "MECH_TSB") (pin "12") (pinfunction "12_12") (pintype "bidirectional"))
    )
    (net (code "392") (name "unconnected-(MECH_TSB-Pad13)") (class "Default")
      (node (ref "MECH_TSB") (pin "13") (pinfunction "13_13") (pintype "bidirectional"))
    )
    (net (code "393") (name "unconnected-(MECH_TSB-Pad14)") (class "Default")
      (node (ref "MECH_TSB") (pin "14") (pinfunction "14_14") (pintype "bidirectional"))
    )
    (net (code "394") (name "unconnected-(MECH_TSB-Pad15)") (class "Default")
      (node (ref "MECH_TSB") (pin "15") (pinfunction "15_15") (pintype "bidirectional"))
    )
    (net (code "395") (name "unconnected-(MECH_TSB-Pad16)") (class "Default")
      (node (ref "MECH_TSB") (pin "16") (pinfunction "16_16") (pintype "bidirectional"))
    )
    (net (code "396") (name "unconnected-(MECH_TSB-Pad17)") (class "Default")
      (node (ref "MECH_TSB") (pin "17") (pinfunction "17_17") (pintype "bidirectional"))
    )
    (net (code "397") (name "unconnected-(MECH_TSB-Pad18)") (class "Default")
      (node (ref "MECH_TSB") (pin "18") (pinfunction "18_18") (pintype "bidirectional"))
    )
    (net (code "398") (name "unconnected-(MECH_TSB-Pad19)") (class "Default")
      (node (ref "MECH_TSB") (pin "19") (pinfunction "19_19") (pintype "bidirectional"))
    )
    (net (code "399") (name "unconnected-(MECH_TSB-Pad20)") (class "Default")
      (node (ref "MECH_TSB") (pin "20") (pinfunction "20_20") (pintype "bidirectional"))
    )
    (net (code "400") (name "unconnected-(MECH_TSB-Pad21)") (class "Default")
      (node (ref "MECH_TSB") (pin "21") (pinfunction "21_21") (pintype "bidirectional"))
    )
    (net (code "401") (name "unconnected-(MECH_TSB-Pad22)") (class "Default")
      (node (ref "MECH_TSB") (pin "22") (pinfunction "22_22") (pintype "bidirectional"))
    )
    (net (code "402") (name "unconnected-(MECH_TSB-Pad23)") (class "Default")
      (node (ref "MECH_TSB") (pin "23") (pinfunction "23_23") (pintype "bidirectional"))
    )
    (net (code "403") (name "unconnected-(MECH_TSB-Pad24)") (class "Default")
      (node (ref "MECH_TSB") (pin "24") (pinfunction "24_24") (pintype "bidirectional"))
    )
    (net (code "404") (name "unconnected-(MECH_TSB-Pad25)") (class "Default")
      (node (ref "MECH_TSB") (pin "25") (pinfunction "25_25") (pintype "bidirectional"))
    )
    (net (code "405") (name "unconnected-(MECH_TSB-Pad26)") (class "Default")
      (node (ref "MECH_TSB") (pin "26") (pinfunction "26_26") (pintype "bidirectional"))
    )
    (net (code "406") (name "unconnected-(MECH_TSB-Pad27)") (class "Default")
      (node (ref "MECH_TSB") (pin "27") (pinfunction "27_27") (pintype "bidirectional"))
    )
    (net (code "407") (name "unconnected-(MECH_TSB-Pad28)") (class "Default")
      (node (ref "MECH_TSB") (pin "28") (pinfunction "28_28") (pintype "bidirectional"))
    )
    (net (code "408") (name "unconnected-(MECH_TSB-Pad29)") (class "Default")
      (node (ref "MECH_TSB") (pin "29") (pinfunction "29_29") (pintype "bidirectional"))
    )
    (net (code "409") (name "unconnected-(MECH_TSB-Pad30)") (class "Default")
      (node (ref "MECH_TSB") (pin "30") (pinfunction "30_30") (pintype "bidirectional"))
    )
    (net (code "410") (name "unconnected-(MECH_TSB-Pad31)") (class "Default")
      (node (ref "MECH_TSB") (pin "31") (pinfunction "31_31") (pintype "bidirectional"))
    )
    (net (code "411") (name "unconnected-(MECH_TSB-Pad32)") (class "Default")
      (node (ref "MECH_TSB") (pin "32") (pinfunction "32_32") (pintype "bidirectional"))
    )
    (net (code "412") (name "unconnected-(MECH_TSB-Pad33)") (class "Default")
      (node (ref "MECH_TSB") (pin "33") (pinfunction "33_33") (pintype "bidirectional"))
    )
    (net (code "413") (name "unconnected-(MECH_TSB-Pad34)") (class "Default")
      (node (ref "MECH_TSB") (pin "34") (pinfunction "34_34") (pintype "bidirectional"))
    )
    (net (code "414") (name "unconnected-(MECH_TSB-Pad35)") (class "Default")
      (node (ref "MECH_TSB") (pin "35") (pinfunction "35_35") (pintype "bidirectional"))
    )
    (net (code "415") (name "unconnected-(MECH_TSB-Pad36)") (class "Default")
      (node (ref "MECH_TSB") (pin "36") (pinfunction "36_36") (pintype "bidirectional"))
    )
    (net (code "416") (name "unconnected-(MECH_TSB-Pad37)") (class "Default")
      (node (ref "MECH_TSB") (pin "37") (pinfunction "37_37") (pintype "bidirectional"))
    )
    (net (code "417") (name "unconnected-(MECH_TSB-Pad38)") (class "Default")
      (node (ref "MECH_TSB") (pin "38") (pinfunction "38_38") (pintype "bidirectional"))
    )
    (net (code "418") (name "unconnected-(MECH_TSB-Pad39)") (class "Default")
      (node (ref "MECH_TSB") (pin "39") (pinfunction "39_39") (pintype "bidirectional"))
    )
    (net (code "419") (name "unconnected-(MECH_TSB-Pad40)") (class "Default")
      (node (ref "MECH_TSB") (pin "40") (pinfunction "40_40") (pintype "bidirectional"))
    )
    (net (code "420") (name "unconnected-(MECH_TSB-Pad41)") (class "Default")
      (node (ref "MECH_TSB") (pin "41") (pinfunction "41_41") (pintype "bidirectional"))
    )
    (net (code "421") (name "unconnected-(MECH_TSB-Pad42)") (class "Default")
      (node (ref "MECH_TSB") (pin "42") (pinfunction "42_42") (pintype "bidirectional"))
    )
    (net (code "422") (name "unconnected-(MECH_TSB-Pad43)") (class "Default")
      (node (ref "MECH_TSB") (pin "43") (pinfunction "43_43") (pintype "bidirectional"))
    )
    (net (code "423") (name "unconnected-(MECH_TSB-Pad44)") (class "Default")
      (node (ref "MECH_TSB") (pin "44") (pinfunction "44_44") (pintype "bidirectional"))
    )
    (net (code "424") (name "unconnected-(MECH_TSB-Pad45)") (class "Default")
      (node (ref "MECH_TSB") (pin "45") (pinfunction "45_45") (pintype "bidirectional"))
    )
    (net (code "425") (name "unconnected-(MECH_TSB-Pad46)") (class "Default")
      (node (ref "MECH_TSB") (pin "46") (pinfunction "46_46") (pintype "bidirectional"))
    )
    (net (code "426") (name "unconnected-(MECH_TSB-Pad47)") (class "Default")
      (node (ref "MECH_TSB") (pin "47") (pinfunction "47_47") (pintype "bidirectional"))
    )
    (net (code "427") (name "unconnected-(MECH_TSB-Pad48)") (class "Default")
      (node (ref "MECH_TSB") (pin "48") (pinfunction "48_48") (pintype "bidirectional"))
    )
    (net (code "428") (name "unconnected-(MECH_TSB-Pad49)") (class "Default")
      (node (ref "MECH_TSB") (pin "49") (pinfunction "49_49") (pintype "bidirectional"))
    )
    (net (code "429") (name "unconnected-(MECH_TSB-Pad50)") (class "Default")
      (node (ref "MECH_TSB") (pin "50") (pinfunction "50_50") (pintype "bidirectional"))
    )
    (net (code "430") (name "unconnected-(MECH_TSB-Pad51)") (class "Default")
      (node (ref "MECH_TSB") (pin "51") (pinfunction "51_51") (pintype "bidirectional"))
    )
    (net (code "431") (name "unconnected-(MECH_TSB-Pad52)") (class "Default")
      (node (ref "MECH_TSB") (pin "52") (pinfunction "52_52") (pintype "bidirectional"))
    )
    (net (code "432") (name "unconnected-(MECH_TSB-Pad53)") (class "Default")
      (node (ref "MECH_TSB") (pin "53") (pinfunction "53_53") (pintype "bidirectional"))
    )
    (net (code "433") (name "unconnected-(MECH_TSB-Pad54)") (class "Default")
      (node (ref "MECH_TSB") (pin "54") (pinfunction "54_54") (pintype "bidirectional"))
    )
    (net (code "434") (name "unconnected-(MECH_TSB-Pad55)") (class "Default")
      (node (ref "MECH_TSB") (pin "55") (pinfunction "55_55") (pintype "bidirectional"))
    )
    (net (code "435") (name "unconnected-(MECH_TSB-Pad56)") (class "Default")
      (node (ref "MECH_TSB") (pin "56") (pinfunction "56_56") (pintype "bidirectional"))
    )
    (net (code "436") (name "unconnected-(MECH_TSB-Pad57)") (class "Default")
      (node (ref "MECH_TSB") (pin "57") (pinfunction "57_57") (pintype "bidirectional"))
    )
    (net (code "437") (name "unconnected-(MECH_TSB-Pad58)") (class "Default")
      (node (ref "MECH_TSB") (pin "58") (pinfunction "58_58") (pintype "bidirectional"))
    )
    (net (code "438") (name "unconnected-(MECH_TSB-Pad59)") (class "Default")
      (node (ref "MECH_TSB") (pin "59") (pinfunction "59_59") (pintype "bidirectional"))
    )
    (net (code "439") (name "unconnected-(MECH_TSB-Pad60)") (class "Default")
      (node (ref "MECH_TSB") (pin "60") (pinfunction "60_60") (pintype "bidirectional"))
    )
    (net (code "440") (name "unconnected-(MECH_TSB-Pad61)") (class "Default")
      (node (ref "MECH_TSB") (pin "61") (pinfunction "61_61") (pintype "bidirectional"))
    )
    (net (code "441") (name "unconnected-(MECH_TSB-Pad62)") (class "Default")
      (node (ref "MECH_TSB") (pin "62") (pinfunction "62_62") (pintype "bidirectional"))
    )
    (net (code "442") (name "unconnected-(MECH_TSB-Pad63)") (class "Default")
      (node (ref "MECH_TSB") (pin "63") (pinfunction "63_63") (pintype "bidirectional"))
    )
    (net (code "443") (name "unconnected-(MECH_TSB-Pad64)") (class "Default")
      (node (ref "MECH_TSB") (pin "64") (pinfunction "64_64") (pintype "bidirectional"))
    )
    (net (code "444") (name "unconnected-(MECH_TSB-Pad65)") (class "Default")
      (node (ref "MECH_TSB") (pin "65") (pinfunction "65_65") (pintype "bidirectional"))
    )
    (net (code "445") (name "unconnected-(MECH_TSB-Pad66)") (class "Default")
      (node (ref "MECH_TSB") (pin "66") (pinfunction "66_66") (pintype "bidirectional"))
    )
    (net (code "446") (name "unconnected-(MECH_TSB-Pad67)") (class "Default")
      (node (ref "MECH_TSB") (pin "67") (pinfunction "67_67") (pintype "bidirectional"))
    )
    (net (code "447") (name "unconnected-(MECH_TSB-Pad68)") (class "Default")
      (node (ref "MECH_TSB") (pin "68") (pinfunction "68_68") (pintype "bidirectional"))
    )
    (net (code "448") (name "unconnected-(MECH_TSB-Pad69)") (class "Default")
      (node (ref "MECH_TSB") (pin "69") (pinfunction "69_69") (pintype "bidirectional"))
    )
    (net (code "449") (name "unconnected-(MECH_TSB-Pad70)") (class "Default")
      (node (ref "MECH_TSB") (pin "70") (pinfunction "70_70") (pintype "bidirectional"))
    )
    (net (code "450") (name "unconnected-(U1-PadNC1)") (class "Default")
      (node (ref "U1") (pin "NC1") (pinfunction "NC1_NC1") (pintype "bidirectional"))
    )
    (net (code "451") (name "unconnected-(U1-PadNC2)") (class "Default")
      (node (ref "U1") (pin "NC2") (pinfunction "NC2_NC2") (pintype "bidirectional"))
    )
    (net (code "452") (name "unconnected-(U1-PadNC3)") (class "Default")
      (node (ref "U1") (pin "NC3") (pinfunction "NC3_NC3") (pintype "bidirectional"))
    )
    (net (code "453") (name "unconnected-(U1-PadNC4)") (class "Default")
      (node (ref "U1") (pin "NC4") (pinfunction "NC4_NC4") (pintype "bidirectional"))
    )
    (net (code "454") (name "unconnected-(U1-PadNC5)") (class "Default")
      (node (ref "U1") (pin "NC5") (pinfunction "NC5_NC5") (pintype "bidirectional"))
    )
    (net (code "455") (name "unconnected-(U1-PadNC6)") (class "Default")
      (node (ref "U1") (pin "NC6") (pinfunction "NC6_NC6") (pintype "bidirectional"))
    )
    (net (code "456") (name "unconnected-(U2-1Y0-Pad12)") (class "Default")
      (node (ref "U2") (pin "12") (pinfunction "1Y0_12") (pintype "bidirectional"))
    )
    (net (code "457") (name "unconnected-(U2-2Y0-Pad2)") (class "Default")
      (node (ref "U2") (pin "2") (pinfunction "2Y0_2") (pintype "bidirectional"))
    )
  )
)
